# RTxController.net
KiCad netlist of a schematic drawn in EAGLE
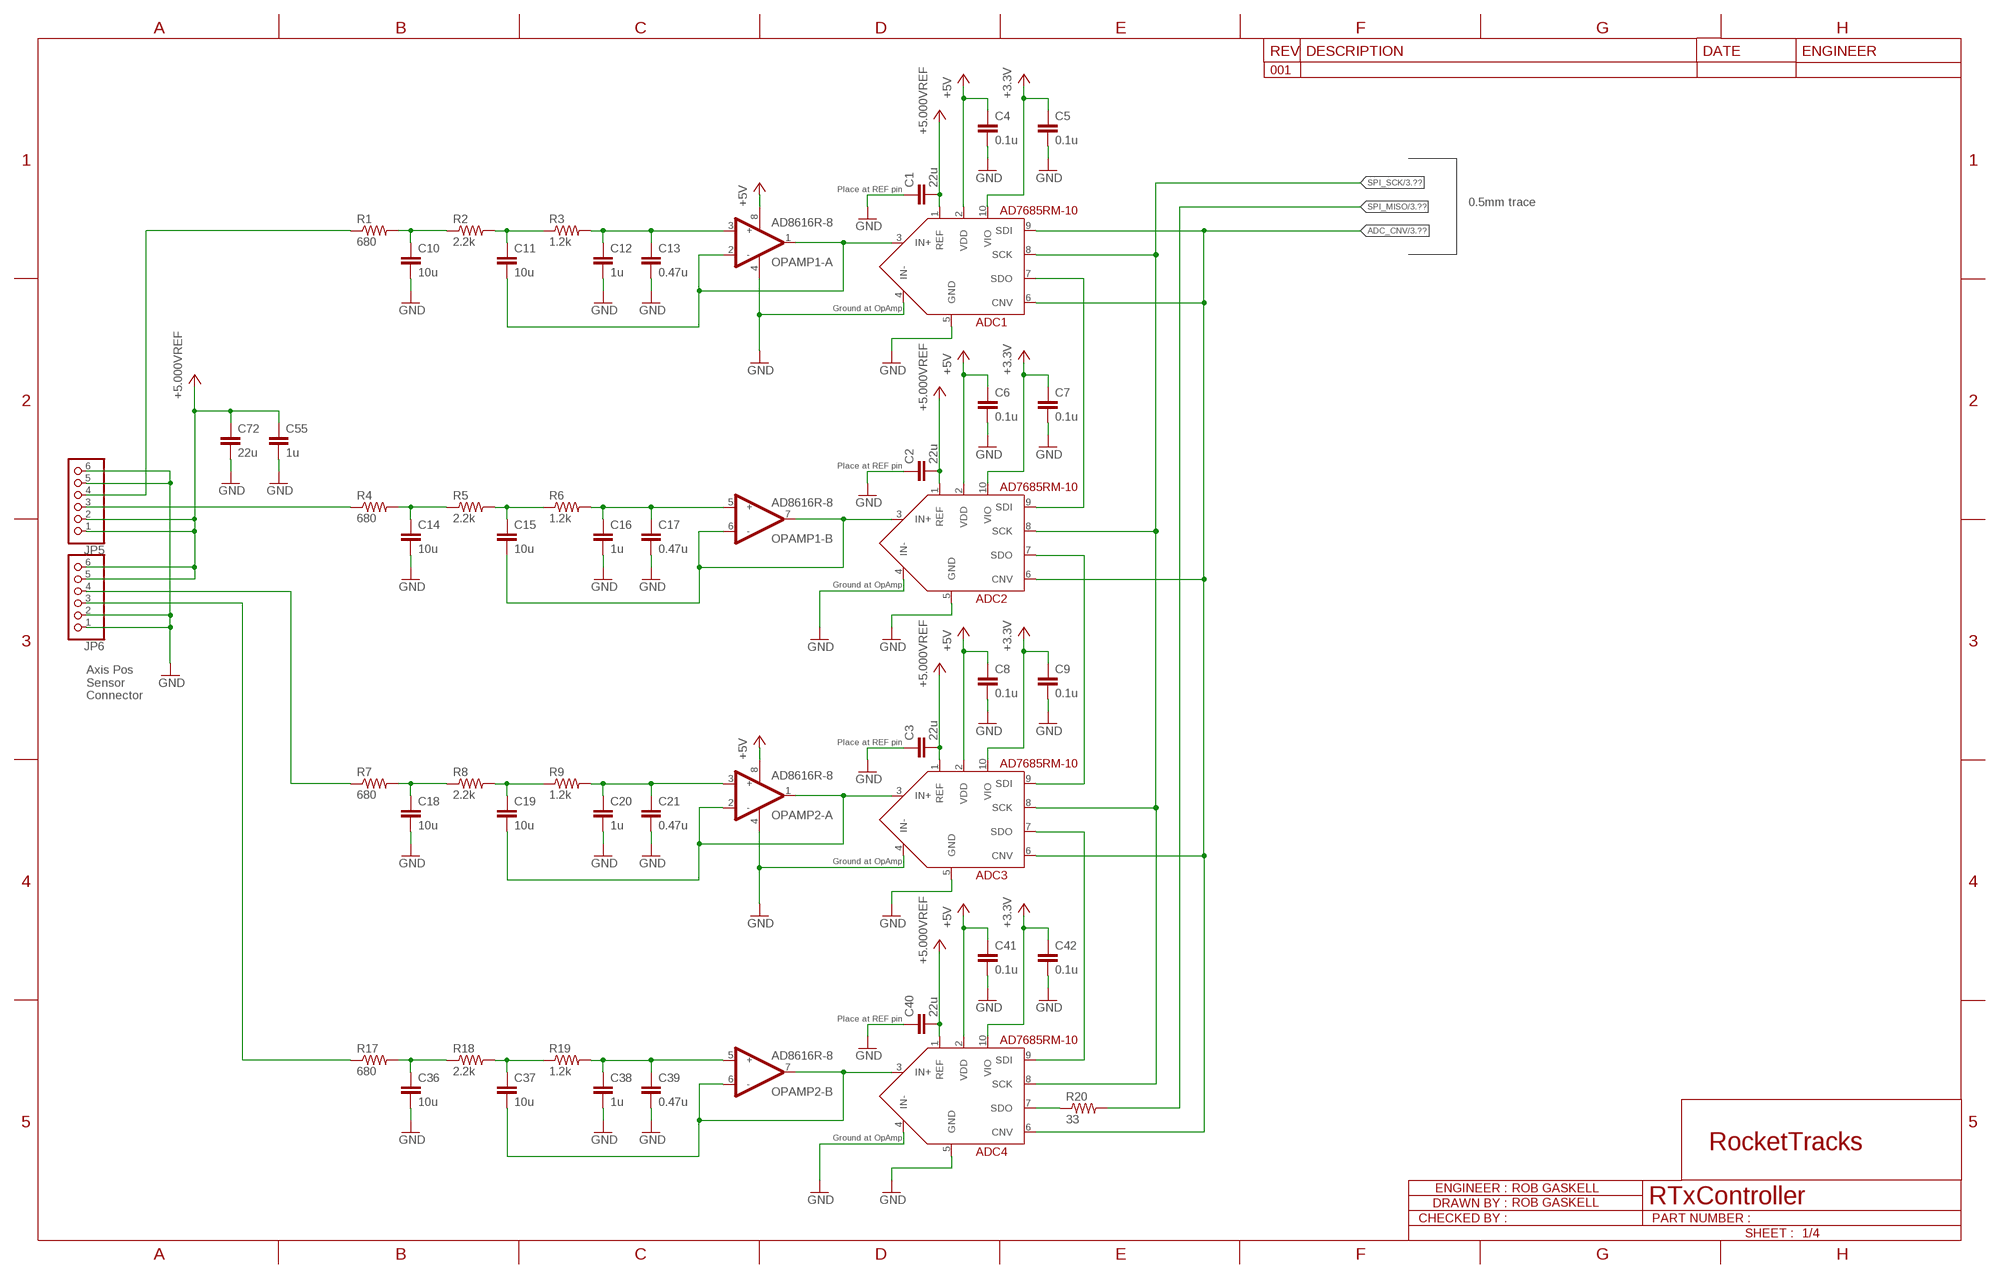
[diagram p0: schematic, sheet 1]
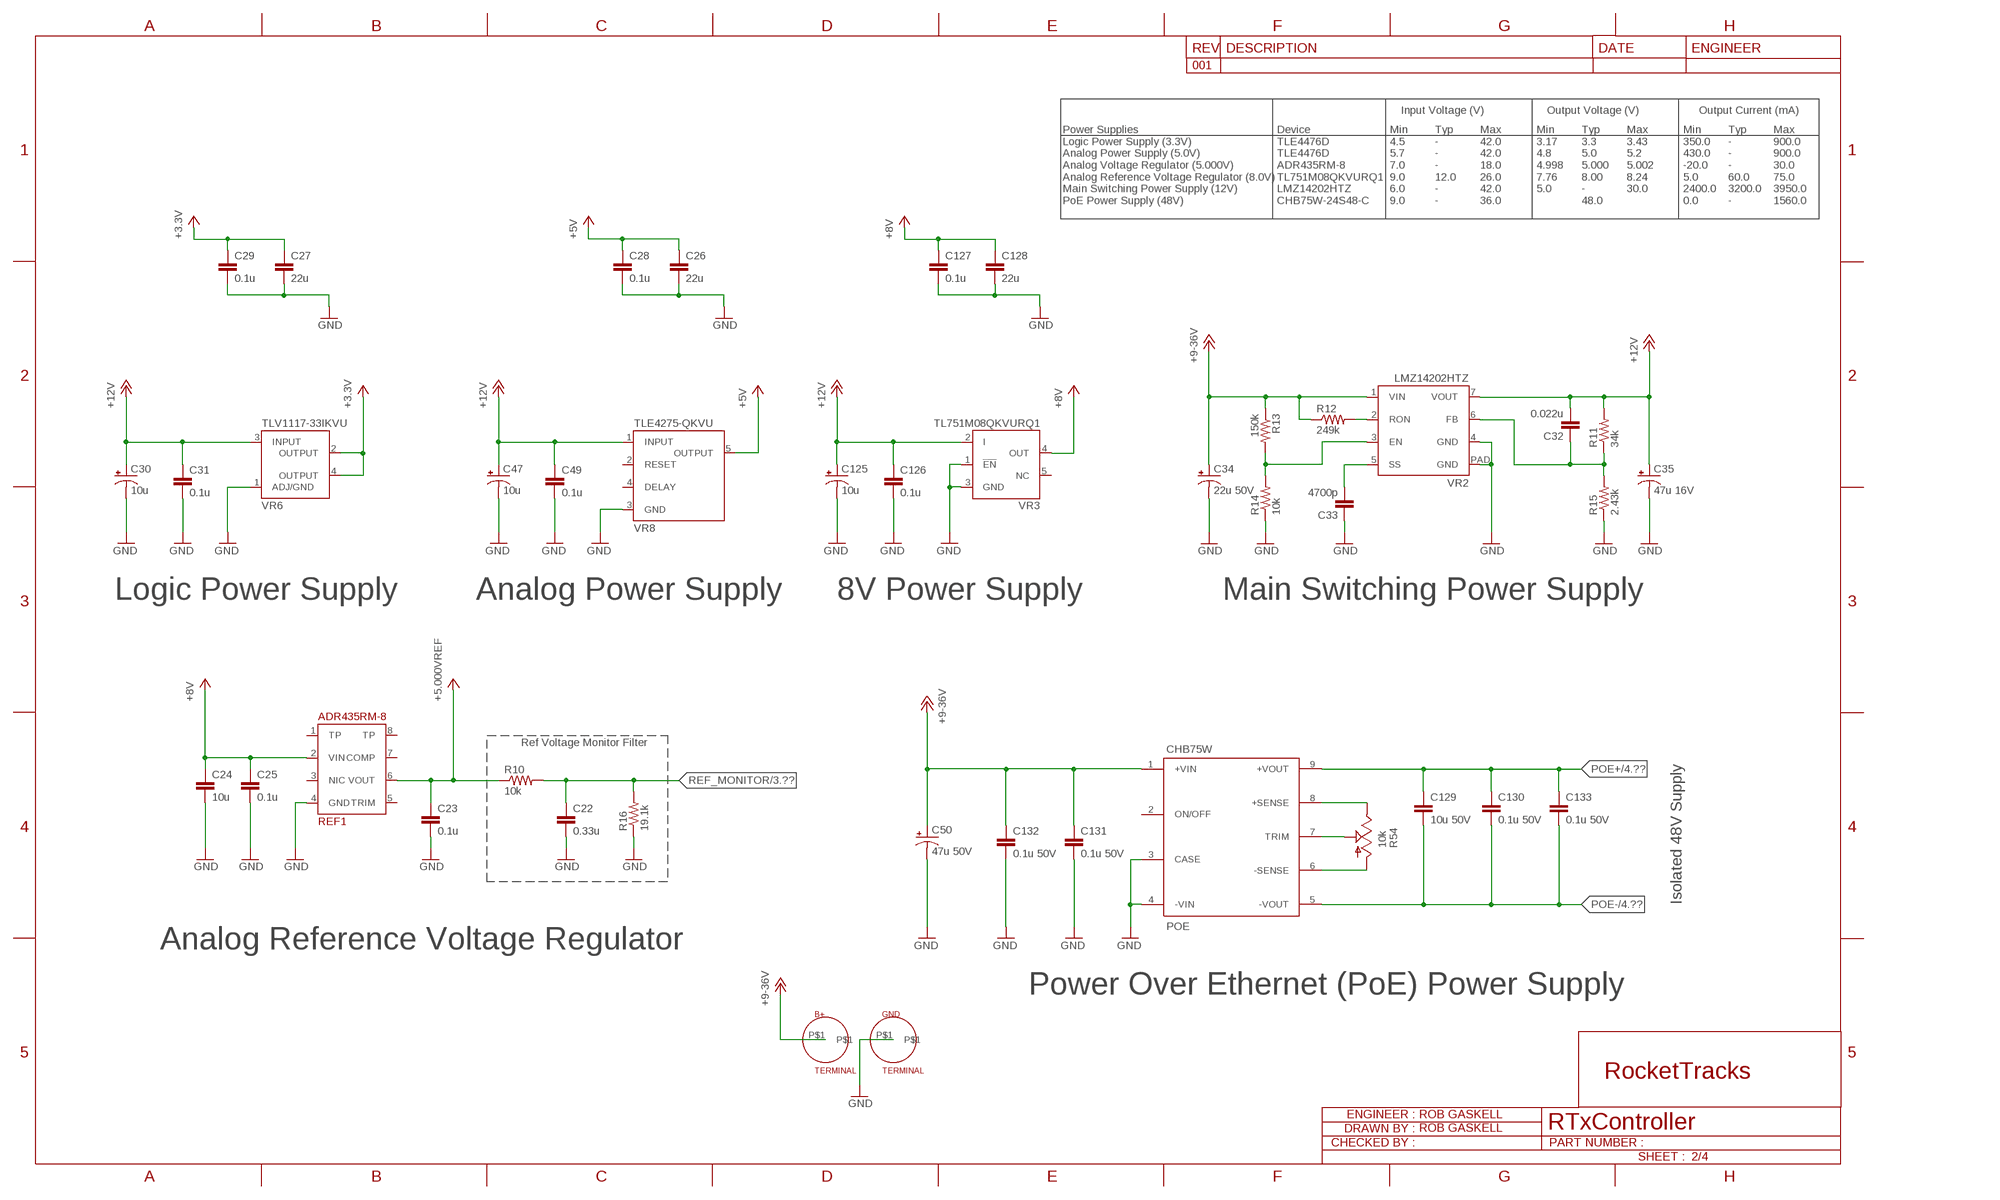
[diagram p1: schematic, sheet 2]
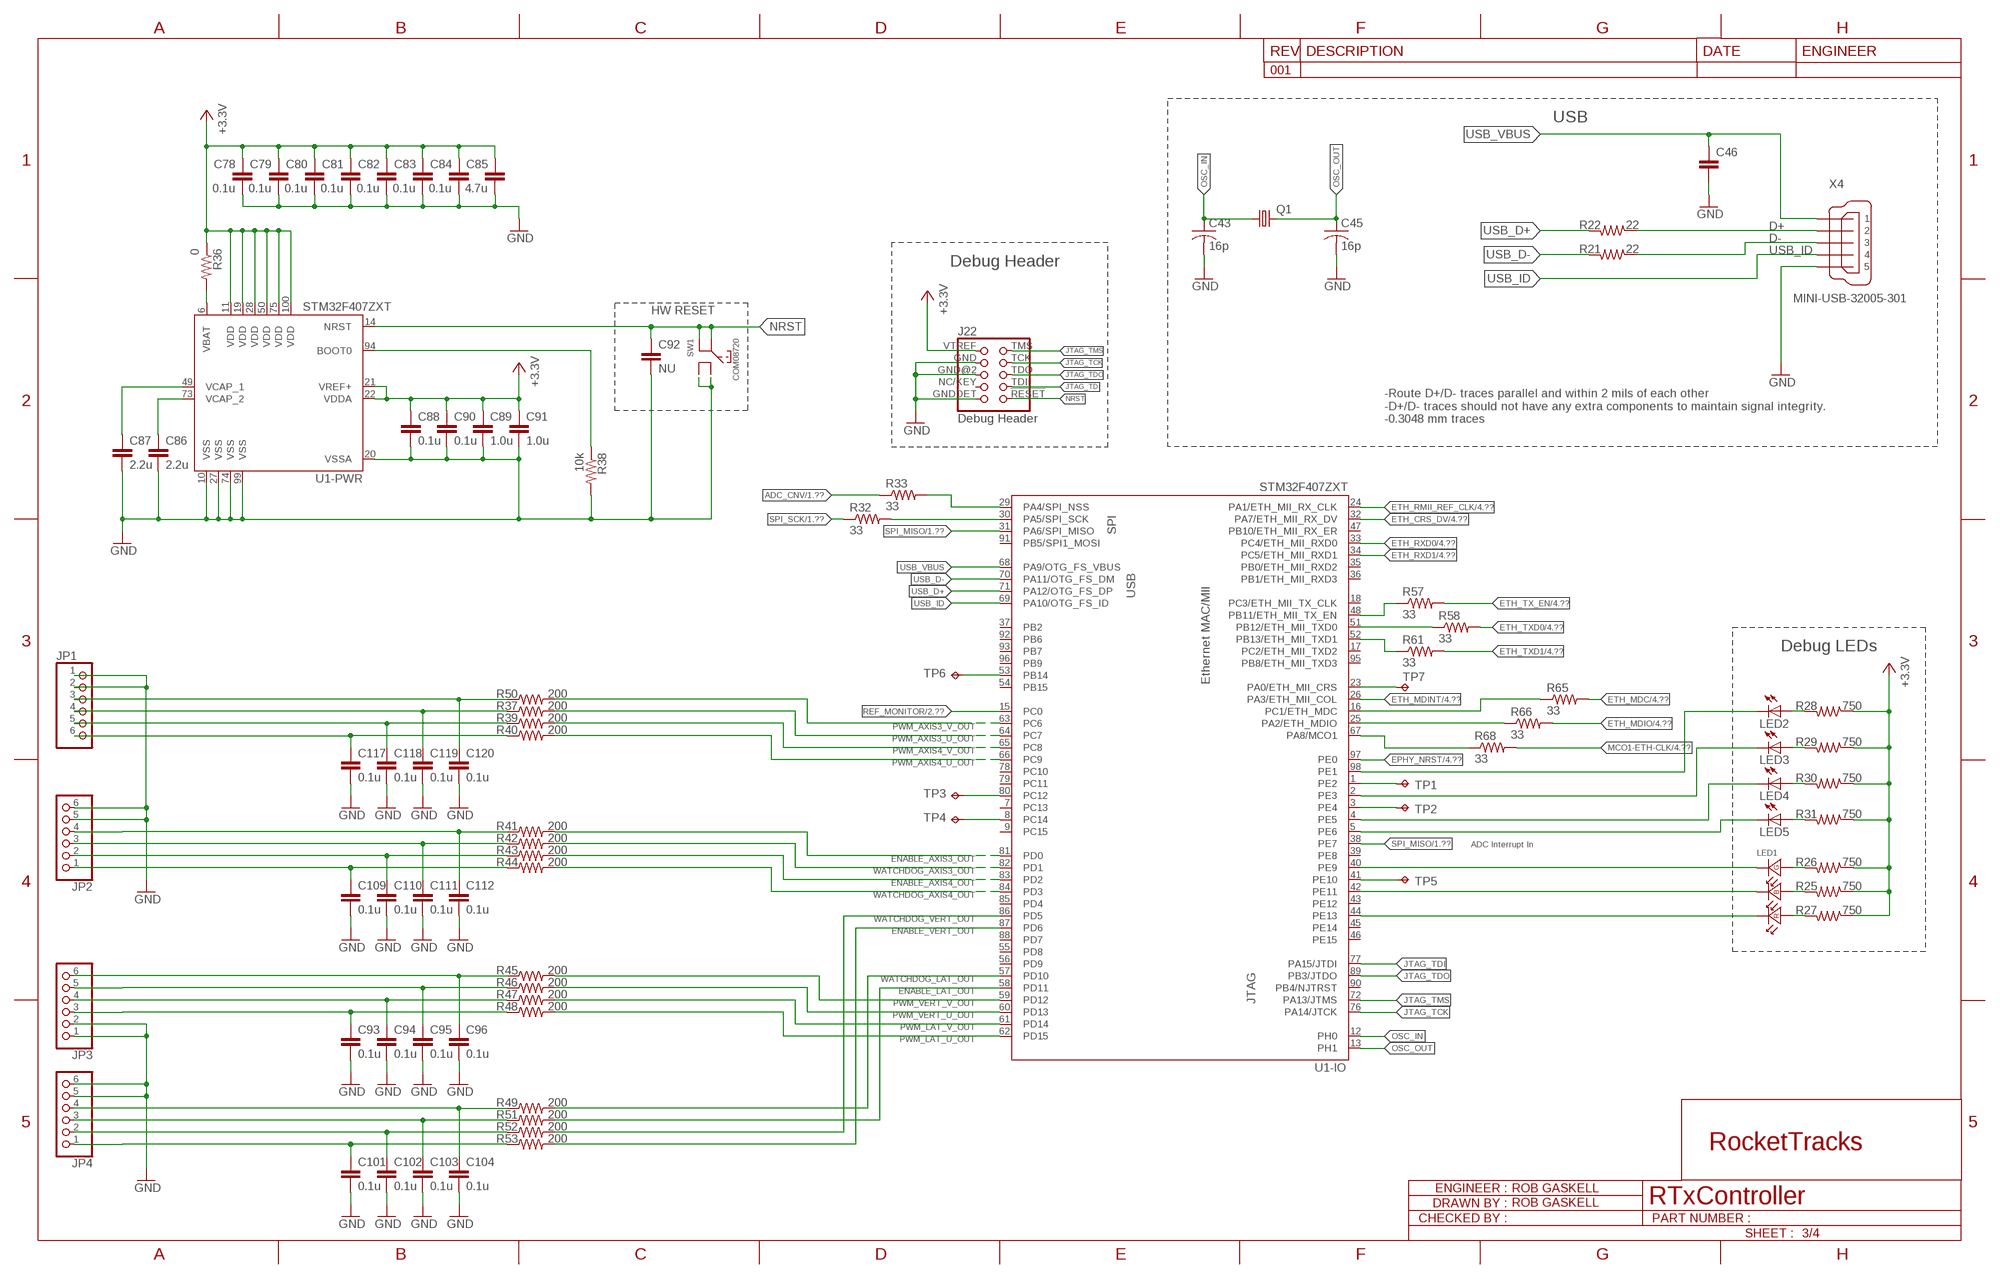
[diagram p2: schematic, sheet 3]
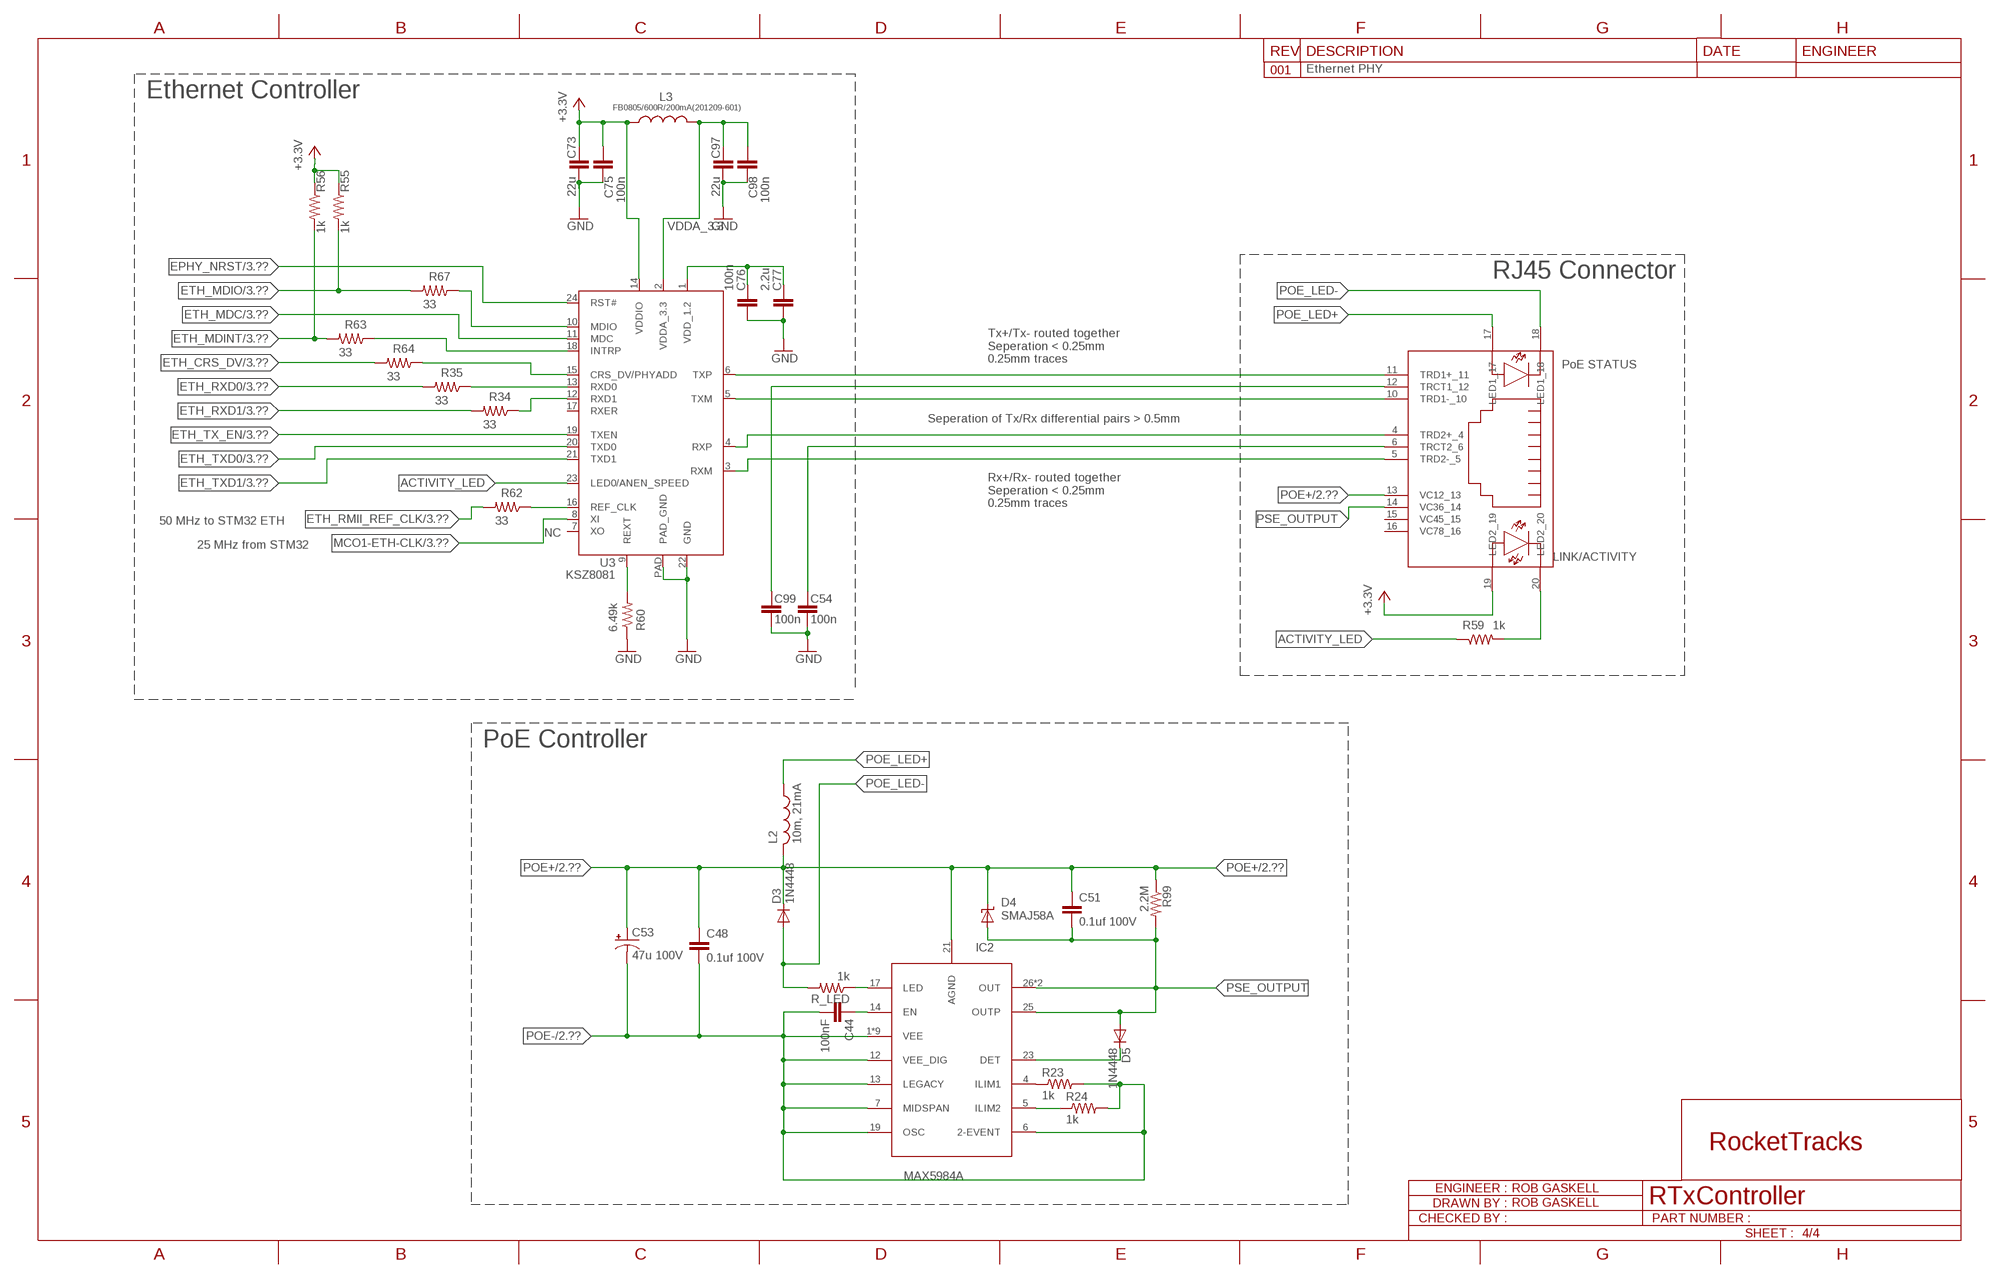
[diagram p3: schematic, sheet 4]

(export (version "E")
  (design (tool "Eeschema 10.0.6"))
  (components
    (comp (ref "C44")
      (value "100nF")
      (footprint "eagle-import:C0805K")
      (libsource (lib "eagle-import") (part "C-EUC0805K"))
    )
    (comp (ref "C48")
      (value "0.1uf 100V")
      (footprint "eagle-import:C0805K")
      (libsource (lib "eagle-import") (part "C-EUC0805K"))
    )
    (comp (ref "C51")
      (value "0.1uf 100V")
      (footprint "eagle-import:C0805K")
      (libsource (lib "eagle-import") (part "C-EUC0805K"))
    )
    (comp (ref "C53")
      (value "47u 100V")
      (footprint "eagle-import:PANASONIC_C")
      (libsource (lib "eagle-import") (part "rcl_CPOL-USC"))
    )
    (comp (ref "C54")
      (value "100n")
      (footprint "eagle-import:0402-C-NOSILK")
      (libsource (lib "eagle-import") (part "C-EU0402-C-NOSILK"))
    )
    (comp (ref "C73")
      (value "22u")
      (footprint "eagle-import:1206-C")
      (libsource (lib "eagle-import") (part "C-EU1206-C"))
    )
    (comp (ref "C75")
      (value "100n")
      (footprint "eagle-import:0402-C-NOSILK")
      (libsource (lib "eagle-import") (part "C-EU0402-C-NOSILK"))
    )
    (comp (ref "C76")
      (value "100n")
      (footprint "eagle-import:0402-C-NOSILK")
      (libsource (lib "eagle-import") (part "C-EU0402-C-NOSILK"))
    )
    (comp (ref "C77")
      (value "2.2u")
      (footprint "eagle-import:0402-C-NOSILK")
      (libsource (lib "eagle-import") (part "C-EU0402-C-NOSILK"))
    )
    (comp (ref "C97")
      (value "22u")
      (footprint "eagle-import:1206-C")
      (libsource (lib "eagle-import") (part "C-EU1206-C"))
    )
    (comp (ref "C98")
      (value "100n")
      (footprint "eagle-import:0402-C-NOSILK")
      (libsource (lib "eagle-import") (part "C-EU0402-C-NOSILK"))
    )
    (comp (ref "C99")
      (value "100n")
      (footprint "eagle-import:0402-C-NOSILK")
      (libsource (lib "eagle-import") (part "C-EU0402-C-NOSILK"))
    )
    (comp (ref "D3")
      (value "1N4448")
      (footprint "eagle-import:SOD-123")
      (libsource (lib "eagle-import") (part "1N4448"))
    )
    (comp (ref "D4")
      (value "SMAJ58A")
      (footprint "eagle-import:SMBJ")
      (libsource (lib "eagle-import") (part "SUPPRESSOR-SMBJ"))
    )
    (comp (ref "D5")
      (value "1N4448")
      (footprint "eagle-import:SOD-123")
      (libsource (lib "eagle-import") (part "1N4448"))
    )
    (comp (ref "IC2")
      (value "MAX5984A")
      (footprint "eagle-import:TQFN-28")
      (libsource (lib "eagle-import") (part "MAX5984"))
    )
    (comp (ref "L2")
      (value "10m, 21mA")
      (footprint "eagle-import:0204V")
      (libsource (lib "eagle-import") (part "L-US0204V"))
    )
    (comp (ref "L3")
      (value "FB0805/600R/200mA(201209-601)")
      (footprint "eagle-import:0805-C-NOSILK")
      (libsource (lib "eagle-import") (part "L-US0805-C-NOSILK"))
    )
    (comp (ref "R23")
      (value "1k")
      (footprint "eagle-import:R0603")
      (libsource (lib "eagle-import") (part "R-US_R0603"))
    )
    (comp (ref "R24")
      (value "1k")
      (footprint "eagle-import:R0603")
      (libsource (lib "eagle-import") (part "R-US_R0603"))
    )
    (comp (ref "R34")
      (value "33")
      (footprint "eagle-import:0402-C-NOSILK")
      (libsource (lib "eagle-import") (part "R-US_0402-C-NOSILK"))
    )
    (comp (ref "R35")
      (value "33")
      (footprint "eagle-import:0402-C-NOSILK")
      (libsource (lib "eagle-import") (part "R-US_0402-C-NOSILK"))
    )
    (comp (ref "R55")
      (value "1k")
      (footprint "eagle-import:0402-C-NOSILK")
      (libsource (lib "eagle-import") (part "R-US_0402-C-NOSILK"))
    )
    (comp (ref "R56")
      (value "1k")
      (footprint "eagle-import:0402-C-NOSILK")
      (libsource (lib "eagle-import") (part "R-US_0402-C-NOSILK"))
    )
    (comp (ref "R59")
      (value "1k")
      (footprint "eagle-import:0402-C-NOSILK")
      (libsource (lib "eagle-import") (part "R-US_0402-C-NOSILK"))
    )
    (comp (ref "R60")
      (value "6.49k")
      (footprint "eagle-import:0402-C-NOSILK")
      (libsource (lib "eagle-import") (part "R-US_0402-C-NOSILK"))
    )
    (comp (ref "R62")
      (value "33")
      (footprint "eagle-import:0402-C-NOSILK")
      (libsource (lib "eagle-import") (part "R-US_0402-C-NOSILK"))
    )
    (comp (ref "R63")
      (value "33")
      (footprint "eagle-import:0402-C-NOSILK")
      (libsource (lib "eagle-import") (part "R-US_0402-C-NOSILK"))
    )
    (comp (ref "R64")
      (value "33")
      (footprint "eagle-import:0402-C-NOSILK")
      (libsource (lib "eagle-import") (part "R-US_0402-C-NOSILK"))
    )
    (comp (ref "R67")
      (value "33")
      (footprint "eagle-import:0402-C-NOSILK")
      (libsource (lib "eagle-import") (part "R-US_0402-C-NOSILK"))
    )
    (comp (ref "R99")
      (value "2.2M")
      (footprint "eagle-import:R0603")
      (libsource (lib "eagle-import") (part "R-US_R0603"))
    )
    (comp (ref "R_LED")
      (value "1k")
      (footprint "eagle-import:R0603")
      (libsource (lib "eagle-import") (part "R-US_R0603"))
    )
    (comp (ref "U3")
      (value "KSZ8081")
      (footprint "eagle-import:QFN-24")
      (libsource (lib "eagle-import") (part "KSZ8081"))
    )
    (comp (ref "X8")
      (value "0826-1X1T-GJ-F")
      (footprint "eagle-import:MAGJACK-RJ45")
      (libsource (lib "eagle-import") (part "0826-1X1T-GJ-F"))
    )
    (comp (ref "B+")
      (value "TERMINAL")
      (footprint "eagle-import:TERMINAL_RELAY")
      (libsource (lib "eagle-import") (part "TERMINAL"))
    )
    (comp (ref "C22")
      (value "0.33u")
      (footprint "eagle-import:C0603")
      (libsource (lib "eagle-import") (part "C-EUC0603"))
    )
    (comp (ref "C23")
      (value "0.1u")
      (footprint "eagle-import:C0402")
      (libsource (lib "eagle-import") (part "C-EUC0402"))
    )
    (comp (ref "C24")
      (value "10u")
      (footprint "eagle-import:C1206")
      (libsource (lib "eagle-import") (part "C-EUC1206"))
    )
    (comp (ref "C25")
      (value "0.1u")
      (footprint "eagle-import:C0402")
      (libsource (lib "eagle-import") (part "C-EUC0402"))
    )
    (comp (ref "C26")
      (value "22u")
      (footprint "eagle-import:C1206")
      (libsource (lib "eagle-import") (part "C-EUC1206"))
    )
    (comp (ref "C27")
      (value "22u")
      (footprint "eagle-import:C1206")
      (libsource (lib "eagle-import") (part "C-EUC1206"))
    )
    (comp (ref "C28")
      (value "0.1u")
      (footprint "eagle-import:C0402")
      (libsource (lib "eagle-import") (part "C-EUC0402"))
    )
    (comp (ref "C29")
      (value "0.1u")
      (footprint "eagle-import:C0402")
      (libsource (lib "eagle-import") (part "C-EUC0402"))
    )
    (comp (ref "C30")
      (value "10u")
      (footprint "eagle-import:PANASONIC_B")
      (libsource (lib "eagle-import") (part "CPOL-USB"))
    )
    (comp (ref "C31")
      (value "0.1u")
      (footprint "eagle-import:C0402")
      (libsource (lib "eagle-import") (part "C-EUC0402"))
    )
    (comp (ref "C32")
      (value "0.022u")
      (footprint "eagle-import:C0402")
      (libsource (lib "eagle-import") (part "C-EUC0402"))
    )
    (comp (ref "C33")
      (value "4700p")
      (footprint "eagle-import:C0402")
      (libsource (lib "eagle-import") (part "C-EUC0402"))
    )
    (comp (ref "C34")
      (value "22u 50V")
      (footprint "eagle-import:PANASONIC_B")
      (libsource (lib "eagle-import") (part "CPOL-USB"))
    )
    (comp (ref "C35")
      (value "47u 16V")
      (footprint "eagle-import:PANASONIC_B")
      (libsource (lib "eagle-import") (part "CPOL-USB"))
    )
    (comp (ref "C47")
      (value "10u")
      (footprint "eagle-import:PANASONIC_B")
      (libsource (lib "eagle-import") (part "CPOL-USB"))
    )
    (comp (ref "C49")
      (value "0.1u")
      (footprint "eagle-import:C0402")
      (libsource (lib "eagle-import") (part "C-EUC0402"))
    )
    (comp (ref "C50")
      (value "47u 50V")
      (footprint "eagle-import:PANASONIC_C")
      (libsource (lib "eagle-import") (part "rcl_CPOL-USC"))
    )
    (comp (ref "C125")
      (value "10u")
      (footprint "eagle-import:PANASONIC_B")
      (libsource (lib "eagle-import") (part "CPOL-USB"))
    )
    (comp (ref "C126")
      (value "0.1u")
      (footprint "eagle-import:C0402")
      (libsource (lib "eagle-import") (part "C-EUC0402"))
    )
    (comp (ref "C127")
      (value "0.1u")
      (footprint "eagle-import:C0402")
      (libsource (lib "eagle-import") (part "C-EUC0402"))
    )
    (comp (ref "C128")
      (value "22u")
      (footprint "eagle-import:C1206")
      (libsource (lib "eagle-import") (part "C-EUC1206"))
    )
    (comp (ref "C129")
      (value "10u 50V")
      (footprint "eagle-import:C1206")
      (libsource (lib "eagle-import") (part "C-EUC1206"))
    )
    (comp (ref "C130")
      (value "0.1u 50V")
      (footprint "eagle-import:C0402")
      (libsource (lib "eagle-import") (part "C-EUC0402"))
    )
    (comp (ref "C131")
      (value "0.1u 50V")
      (footprint "eagle-import:C0402")
      (libsource (lib "eagle-import") (part "C-EUC0402"))
    )
    (comp (ref "C132")
      (value "0.1u 50V")
      (footprint "eagle-import:C0402")
      (libsource (lib "eagle-import") (part "C-EUC0402"))
    )
    (comp (ref "C133")
      (value "0.1u 50V")
      (footprint "eagle-import:C0402")
      (libsource (lib "eagle-import") (part "C-EUC0402"))
    )
    (comp (ref "GND")
      (value "TERMINAL")
      (footprint "eagle-import:TERMINAL_RELAY")
      (libsource (lib "eagle-import") (part "TERMINAL"))
    )
    (comp (ref "POE")
      (value "CHB75W")
      (footprint "eagle-import:CHB75W")
      (libsource (lib "eagle-import") (part "CHB75W"))
    )
    (comp (ref "R10")
      (value "10k")
      (footprint "eagle-import:R0402")
      (libsource (lib "eagle-import") (part "R-US_R0402"))
    )
    (comp (ref "R11")
      (value "34k")
      (footprint "eagle-import:R0603")
      (libsource (lib "eagle-import") (part "R-US_R0603"))
    )
    (comp (ref "R12")
      (value "249k")
      (footprint "eagle-import:R0603")
      (libsource (lib "eagle-import") (part "R-US_R0603"))
    )
    (comp (ref "R13")
      (value "150k")
      (footprint "eagle-import:R0603")
      (libsource (lib "eagle-import") (part "R-US_R0603"))
    )
    (comp (ref "R14")
      (value "10k")
      (footprint "eagle-import:R0603")
      (libsource (lib "eagle-import") (part "R-US_R0603"))
    )
    (comp (ref "R15")
      (value "2.43k")
      (footprint "eagle-import:R0603")
      (libsource (lib "eagle-import") (part "R-US_R0603"))
    )
    (comp (ref "R16")
      (value "19.1k")
      (footprint "eagle-import:R0402")
      (libsource (lib "eagle-import") (part "R-US_R0402"))
    )
    (comp (ref "R54")
      (value "10k")
      (footprint "eagle-import:3223W")
      (libsource (lib "eagle-import") (part "TRIM_US-3223W"))
    )
    (comp (ref "REF1")
      (value "ADR435RM-8")
      (footprint "eagle-import:SOIC8")
      (libsource (lib "eagle-import") (part "ADR435RM-8"))
    )
    (comp (ref "VR2")
      (value "LMZ14202HTZ")
      (footprint "eagle-import:PFM-7")
      (libsource (lib "eagle-import") (part "LMZ14202HTZ"))
    )
    (comp (ref "VR3")
      (value "TL751M08QKVURQ1")
      (footprint "eagle-import:PG-TO252-5-11")
      (libsource (lib "eagle-import") (part "TL751M08QKVURQ1"))
    )
    (comp (ref "VR6")
      (value "TLV1117-33IKVU")
      (footprint "eagle-import:PG-TO252-3-11")
      (libsource (lib "eagle-import") (part "TLV1117-33IKVU"))
    )
    (comp (ref "VR8")
      (value "TLE4275-QKVU")
      (footprint "eagle-import:PG-TO252-5-11")
      (libsource (lib "eagle-import") (part "TLE4275-QKVU"))
    )
    (comp (ref "ADC1")
      (value "AD7685RM-10")
      (footprint "eagle-import:MSOP-10")
      (libsource (lib "eagle-import") (part "AD7685RM-10"))
    )
    (comp (ref "ADC2")
      (value "AD7685RM-10")
      (footprint "eagle-import:MSOP-10")
      (libsource (lib "eagle-import") (part "AD7685RM-10"))
    )
    (comp (ref "ADC3")
      (value "AD7685RM-10")
      (footprint "eagle-import:MSOP-10")
      (libsource (lib "eagle-import") (part "AD7685RM-10"))
    )
    (comp (ref "ADC4")
      (value "AD7685RM-10")
      (footprint "eagle-import:MSOP-10")
      (libsource (lib "eagle-import") (part "AD7685RM-10"))
    )
    (comp (ref "C1")
      (value "22u")
      (footprint "eagle-import:C1206")
      (libsource (lib "eagle-import") (part "C-EUC1206"))
    )
    (comp (ref "C2")
      (value "22u")
      (footprint "eagle-import:C1206")
      (libsource (lib "eagle-import") (part "C-EUC1206"))
    )
    (comp (ref "C3")
      (value "22u")
      (footprint "eagle-import:C1206")
      (libsource (lib "eagle-import") (part "C-EUC1206"))
    )
    (comp (ref "C4")
      (value "0.1u")
      (footprint "eagle-import:C0402")
      (libsource (lib "eagle-import") (part "C-EUC0402"))
    )
    (comp (ref "C5")
      (value "0.1u")
      (footprint "eagle-import:C0402")
      (libsource (lib "eagle-import") (part "C-EUC0402"))
    )
    (comp (ref "C6")
      (value "0.1u")
      (footprint "eagle-import:C0402")
      (libsource (lib "eagle-import") (part "C-EUC0402"))
    )
    (comp (ref "C7")
      (value "0.1u")
      (footprint "eagle-import:C0402")
      (libsource (lib "eagle-import") (part "C-EUC0402"))
    )
    (comp (ref "C8")
      (value "0.1u")
      (footprint "eagle-import:C0402")
      (libsource (lib "eagle-import") (part "C-EUC0402"))
    )
    (comp (ref "C9")
      (value "0.1u")
      (footprint "eagle-import:C0402")
      (libsource (lib "eagle-import") (part "C-EUC0402"))
    )
    (comp (ref "C10")
      (value "10u")
      (footprint "eagle-import:C1206")
      (libsource (lib "eagle-import") (part "C-EUC1206"))
    )
    (comp (ref "C11")
      (value "10u")
      (footprint "eagle-import:C1206")
      (libsource (lib "eagle-import") (part "C-EUC1206"))
    )
    (comp (ref "C12")
      (value "1u")
      (footprint "eagle-import:C0805")
      (libsource (lib "eagle-import") (part "C-EUC0805"))
    )
    (comp (ref "C13")
      (value "0.47u")
      (footprint "eagle-import:C0805")
      (libsource (lib "eagle-import") (part "C-EUC0805"))
    )
    (comp (ref "C14")
      (value "10u")
      (footprint "eagle-import:C1206")
      (libsource (lib "eagle-import") (part "C-EUC1206"))
    )
    (comp (ref "C15")
      (value "10u")
      (footprint "eagle-import:C1206")
      (libsource (lib "eagle-import") (part "C-EUC1206"))
    )
    (comp (ref "C16")
      (value "1u")
      (footprint "eagle-import:C0805")
      (libsource (lib "eagle-import") (part "C-EUC0805"))
    )
    (comp (ref "C17")
      (value "0.47u")
      (footprint "eagle-import:C0805")
      (libsource (lib "eagle-import") (part "C-EUC0805"))
    )
    (comp (ref "C18")
      (value "10u")
      (footprint "eagle-import:C1206")
      (libsource (lib "eagle-import") (part "C-EUC1206"))
    )
    (comp (ref "C19")
      (value "10u")
      (footprint "eagle-import:C1206")
      (libsource (lib "eagle-import") (part "C-EUC1206"))
    )
    (comp (ref "C20")
      (value "1u")
      (footprint "eagle-import:C0805")
      (libsource (lib "eagle-import") (part "C-EUC0805"))
    )
    (comp (ref "C21")
      (value "0.47u")
      (footprint "eagle-import:C0805")
      (libsource (lib "eagle-import") (part "C-EUC0805"))
    )
    (comp (ref "C36")
      (value "10u")
      (footprint "eagle-import:C1206")
      (libsource (lib "eagle-import") (part "C-EUC1206"))
    )
    (comp (ref "C37")
      (value "10u")
      (footprint "eagle-import:C1206")
      (libsource (lib "eagle-import") (part "C-EUC1206"))
    )
    (comp (ref "C38")
      (value "1u")
      (footprint "eagle-import:C0805")
      (libsource (lib "eagle-import") (part "C-EUC0805"))
    )
    (comp (ref "C39")
      (value "0.47u")
      (footprint "eagle-import:C0805")
      (libsource (lib "eagle-import") (part "C-EUC0805"))
    )
    (comp (ref "C40")
      (value "22u")
      (footprint "eagle-import:C1206")
      (libsource (lib "eagle-import") (part "C-EUC1206"))
    )
    (comp (ref "C41")
      (value "0.1u")
      (footprint "eagle-import:C0402")
      (libsource (lib "eagle-import") (part "C-EUC0402"))
    )
    (comp (ref "C42")
      (value "0.1u")
      (footprint "eagle-import:C0402")
      (libsource (lib "eagle-import") (part "C-EUC0402"))
    )
    (comp (ref "C55")
      (value "1u")
      (footprint "eagle-import:C0805")
      (libsource (lib "eagle-import") (part "C-EUC0805"))
    )
    (comp (ref "C72")
      (value "22u")
      (footprint "eagle-import:C1206")
      (libsource (lib "eagle-import") (part "C-EUC1206"))
    )
    (comp (ref "JP5")
      (value "PINHD-1X6")
      (footprint "eagle-import:1X06")
      (libsource (lib "eagle-import") (part "PINHD-1X6"))
    )
    (comp (ref "JP6")
      (value "PINHD-1X6")
      (footprint "eagle-import:1X06")
      (libsource (lib "eagle-import") (part "PINHD-1X6"))
    )
    (comp (ref "OPAMP1")
      (value "AD8616R-8")
      (footprint "eagle-import:SOIC8")
      (libsource (lib "eagle-import") (part "AD8616R-8"))
    )
    (comp (ref "OPAMP2")
      (value "AD8616R-8")
      (footprint "eagle-import:SOIC8")
      (libsource (lib "eagle-import") (part "AD8616R-8"))
    )
    (comp (ref "R1")
      (value "680")
      (footprint "eagle-import:R0402")
      (libsource (lib "eagle-import") (part "R-US_R0402"))
    )
    (comp (ref "R2")
      (value "2.2k")
      (footprint "eagle-import:R0402")
      (libsource (lib "eagle-import") (part "R-US_R0402"))
    )
    (comp (ref "R3")
      (value "1.2k")
      (footprint "eagle-import:R0402")
      (libsource (lib "eagle-import") (part "R-US_R0402"))
    )
    (comp (ref "R4")
      (value "680")
      (footprint "eagle-import:R0402")
      (libsource (lib "eagle-import") (part "R-US_R0402"))
    )
    (comp (ref "R5")
      (value "2.2k")
      (footprint "eagle-import:R0402")
      (libsource (lib "eagle-import") (part "R-US_R0402"))
    )
    (comp (ref "R6")
      (value "1.2k")
      (footprint "eagle-import:R0402")
      (libsource (lib "eagle-import") (part "R-US_R0402"))
    )
    (comp (ref "R7")
      (value "680")
      (footprint "eagle-import:R0402")
      (libsource (lib "eagle-import") (part "R-US_R0402"))
    )
    (comp (ref "R8")
      (value "2.2k")
      (footprint "eagle-import:R0402")
      (libsource (lib "eagle-import") (part "R-US_R0402"))
    )
    (comp (ref "R9")
      (value "1.2k")
      (footprint "eagle-import:R0402")
      (libsource (lib "eagle-import") (part "R-US_R0402"))
    )
    (comp (ref "R17")
      (value "680")
      (footprint "eagle-import:R0402")
      (libsource (lib "eagle-import") (part "R-US_R0402"))
    )
    (comp (ref "R18")
      (value "2.2k")
      (footprint "eagle-import:R0402")
      (libsource (lib "eagle-import") (part "R-US_R0402"))
    )
    (comp (ref "R19")
      (value "1.2k")
      (footprint "eagle-import:R0402")
      (libsource (lib "eagle-import") (part "R-US_R0402"))
    )
    (comp (ref "R20")
      (value "33")
      (footprint "eagle-import:R0402")
      (libsource (lib "eagle-import") (part "R-US_R0402"))
    )
    (comp (ref "C43")
      (value "16p")
      (footprint "eagle-import:C0402")
      (libsource (lib "eagle-import") (part "C-USC0402"))
    )
    (comp (ref "C45")
      (value "16p")
      (footprint "eagle-import:C0402")
      (libsource (lib "eagle-import") (part "C-USC0402"))
    )
    (comp (ref "C46")
      (value "C-EUC0603")
      (footprint "eagle-import:C0603")
      (libsource (lib "eagle-import") (part "rcl_C-EUC0603"))
    )
    (comp (ref "C78")
      (value "0.1u")
      (footprint "eagle-import:C0402")
      (libsource (lib "eagle-import") (part "C-EUC0402"))
    )
    (comp (ref "C79")
      (value "0.1u")
      (footprint "eagle-import:C0402")
      (libsource (lib "eagle-import") (part "C-EUC0402"))
    )
    (comp (ref "C80")
      (value "0.1u")
      (footprint "eagle-import:C0402")
      (libsource (lib "eagle-import") (part "C-EUC0402"))
    )
    (comp (ref "C81")
      (value "0.1u")
      (footprint "eagle-import:C0402")
      (libsource (lib "eagle-import") (part "C-EUC0402"))
    )
    (comp (ref "C82")
      (value "0.1u")
      (footprint "eagle-import:C0402")
      (libsource (lib "eagle-import") (part "C-EUC0402"))
    )
    (comp (ref "C83")
      (value "0.1u")
      (footprint "eagle-import:C0402")
      (libsource (lib "eagle-import") (part "C-EUC0402"))
    )
    (comp (ref "C84")
      (value "0.1u")
      (footprint "eagle-import:C0402")
      (libsource (lib "eagle-import") (part "C-EUC0402"))
    )
    (comp (ref "C85")
      (value "4.7u")
      (footprint "eagle-import:C0603")
      (libsource (lib "eagle-import") (part "C-EUC0603"))
    )
    (comp (ref "C86")
      (value "2.2u")
      (footprint "eagle-import:C0402")
      (libsource (lib "eagle-import") (part "C-EUC0402"))
    )
    (comp (ref "C87")
      (value "2.2u")
      (footprint "eagle-import:C0402")
      (libsource (lib "eagle-import") (part "C-EUC0402"))
    )
    (comp (ref "C88")
      (value "0.1u")
      (footprint "eagle-import:C0402")
      (libsource (lib "eagle-import") (part "C-EUC0402"))
    )
    (comp (ref "C89")
      (value "1.0u")
      (footprint "eagle-import:C0402")
      (libsource (lib "eagle-import") (part "C-EUC0402"))
    )
    (comp (ref "C90")
      (value "0.1u")
      (footprint "eagle-import:C0402")
      (libsource (lib "eagle-import") (part "C-EUC0402"))
    )
    (comp (ref "C91")
      (value "1.0u")
      (footprint "eagle-import:C0402")
      (libsource (lib "eagle-import") (part "C-EUC0402"))
    )
    (comp (ref "C92")
      (value "NU")
      (footprint "eagle-import:C0402")
      (libsource (lib "eagle-import") (part "C-EUC0402"))
    )
    (comp (ref "C93")
      (value "0.1u")
      (footprint "eagle-import:C0603")
      (libsource (lib "eagle-import") (part "C-EUC0603"))
    )
    (comp (ref "C94")
      (value "0.1u")
      (footprint "eagle-import:C0603")
      (libsource (lib "eagle-import") (part "C-EUC0603"))
    )
    (comp (ref "C95")
      (value "0.1u")
      (footprint "eagle-import:C0603")
      (libsource (lib "eagle-import") (part "C-EUC0603"))
    )
    (comp (ref "C96")
      (value "0.1u")
      (footprint "eagle-import:C0603")
      (libsource (lib "eagle-import") (part "C-EUC0603"))
    )
    (comp (ref "C101")
      (value "0.1u")
      (footprint "eagle-import:C0603")
      (libsource (lib "eagle-import") (part "C-EUC0603"))
    )
    (comp (ref "C102")
      (value "0.1u")
      (footprint "eagle-import:C0603")
      (libsource (lib "eagle-import") (part "C-EUC0603"))
    )
    (comp (ref "C103")
      (value "0.1u")
      (footprint "eagle-import:C0603")
      (libsource (lib "eagle-import") (part "C-EUC0603"))
    )
    (comp (ref "C104")
      (value "0.1u")
      (footprint "eagle-import:C0603")
      (libsource (lib "eagle-import") (part "C-EUC0603"))
    )
    (comp (ref "C109")
      (value "0.1u")
      (footprint "eagle-import:C0603")
      (libsource (lib "eagle-import") (part "C-EUC0603"))
    )
    (comp (ref "C110")
      (value "0.1u")
      (footprint "eagle-import:C0603")
      (libsource (lib "eagle-import") (part "C-EUC0603"))
    )
    (comp (ref "C111")
      (value "0.1u")
      (footprint "eagle-import:C0603")
      (libsource (lib "eagle-import") (part "C-EUC0603"))
    )
    (comp (ref "C112")
      (value "0.1u")
      (footprint "eagle-import:C0603")
      (libsource (lib "eagle-import") (part "C-EUC0603"))
    )
    (comp (ref "C117")
      (value "0.1u")
      (footprint "eagle-import:C0603")
      (libsource (lib "eagle-import") (part "C-EUC0603"))
    )
    (comp (ref "C118")
      (value "0.1u")
      (footprint "eagle-import:C0603")
      (libsource (lib "eagle-import") (part "C-EUC0603"))
    )
    (comp (ref "C119")
      (value "0.1u")
      (footprint "eagle-import:C0603")
      (libsource (lib "eagle-import") (part "C-EUC0603"))
    )
    (comp (ref "C120")
      (value "0.1u")
      (footprint "eagle-import:C0603")
      (libsource (lib "eagle-import") (part "C-EUC0603"))
    )
    (comp (ref "J22")
      (value "Debug Header")
      (footprint "eagle-import:1.27MM_2X5")
      (libsource (lib "eagle-import") (part "1.27MM_HDR_2X5"))
    )
    (comp (ref "JP1")
      (value "PINHD-1X6")
      (footprint "eagle-import:1X06")
      (libsource (lib "eagle-import") (part "PINHD-1X6"))
    )
    (comp (ref "JP2")
      (value "PINHD-1X6")
      (footprint "eagle-import:1X06")
      (libsource (lib "eagle-import") (part "PINHD-1X6"))
    )
    (comp (ref "JP3")
      (value "PINHD-1X6")
      (footprint "eagle-import:1X06")
      (libsource (lib "eagle-import") (part "PINHD-1X6"))
    )
    (comp (ref "JP4")
      (value "PINHD-1X6")
      (footprint "eagle-import:1X06")
      (libsource (lib "eagle-import") (part "PINHD-1X6"))
    )
    (comp (ref "LED1")
      (value "LED_RGB_PLCC-6")
      (footprint "eagle-import:PLCC-6")
      (libsource (lib "eagle-import") (part "LED_RGB_PLCC-6"))
    )
    (comp (ref "LED2")
      (value "LEDCHIP-LED0603")
      (footprint "eagle-import:CHIP-LED0603")
      (libsource (lib "eagle-import") (part "LEDCHIP-LED0603"))
    )
    (comp (ref "LED3")
      (value "LEDCHIP-LED0603")
      (footprint "eagle-import:CHIP-LED0603")
      (libsource (lib "eagle-import") (part "LEDCHIP-LED0603"))
    )
    (comp (ref "LED4")
      (value "LEDCHIP-LED0603")
      (footprint "eagle-import:CHIP-LED0603")
      (libsource (lib "eagle-import") (part "LEDCHIP-LED0603"))
    )
    (comp (ref "LED5")
      (value "LEDCHIP-LED0603")
      (footprint "eagle-import:CHIP-LED0603")
      (libsource (lib "eagle-import") (part "LEDCHIP-LED0603"))
    )
    (comp (ref "Q1")
      (value "CRYSTALCTS406")
      (footprint "eagle-import:CTS406")
      (libsource (lib "eagle-import") (part "CRYSTALCTS406"))
    )
    (comp (ref "R21")
      (value "22")
      (footprint "eagle-import:R0402")
      (libsource (lib "eagle-import") (part "rcl_R-US_R0402"))
    )
    (comp (ref "R22")
      (value "22")
      (footprint "eagle-import:R0402")
      (libsource (lib "eagle-import") (part "rcl_R-US_R0402"))
    )
    (comp (ref "R25")
      (value "750")
      (footprint "eagle-import:R0402")
      (libsource (lib "eagle-import") (part "rcl_R-US_R0402"))
    )
    (comp (ref "R26")
      (value "750")
      (footprint "eagle-import:R0402")
      (libsource (lib "eagle-import") (part "rcl_R-US_R0402"))
    )
    (comp (ref "R27")
      (value "750")
      (footprint "eagle-import:R0402")
      (libsource (lib "eagle-import") (part "rcl_R-US_R0402"))
    )
    (comp (ref "R28")
      (value "750")
      (footprint "eagle-import:R0402")
      (libsource (lib "eagle-import") (part "rcl_R-US_R0402"))
    )
    (comp (ref "R29")
      (value "750")
      (footprint "eagle-import:R0402")
      (libsource (lib "eagle-import") (part "rcl_R-US_R0402"))
    )
    (comp (ref "R30")
      (value "750")
      (footprint "eagle-import:R0402")
      (libsource (lib "eagle-import") (part "rcl_R-US_R0402"))
    )
    (comp (ref "R31")
      (value "750")
      (footprint "eagle-import:R0402")
      (libsource (lib "eagle-import") (part "rcl_R-US_R0402"))
    )
    (comp (ref "R32")
      (value "33")
      (footprint "eagle-import:R0402")
      (libsource (lib "eagle-import") (part "R-US_R0402"))
    )
    (comp (ref "R33")
      (value "33")
      (footprint "eagle-import:R0402")
      (libsource (lib "eagle-import") (part "R-US_R0402"))
    )
    (comp (ref "R36")
      (value "0")
      (footprint "eagle-import:R0603")
      (libsource (lib "eagle-import") (part "R-US_R0603"))
    )
    (comp (ref "R37")
      (value "200")
      (footprint "eagle-import:R0603")
      (libsource (lib "eagle-import") (part "R-US_R0603"))
    )
    (comp (ref "R38")
      (value "10k")
      (footprint "eagle-import:R0603")
      (libsource (lib "eagle-import") (part "R-US_R0603"))
    )
    (comp (ref "R39")
      (value "200")
      (footprint "eagle-import:R0603")
      (libsource (lib "eagle-import") (part "R-US_R0603"))
    )
    (comp (ref "R40")
      (value "200")
      (footprint "eagle-import:R0603")
      (libsource (lib "eagle-import") (part "R-US_R0603"))
    )
    (comp (ref "R41")
      (value "200")
      (footprint "eagle-import:R0603")
      (libsource (lib "eagle-import") (part "R-US_R0603"))
    )
    (comp (ref "R42")
      (value "200")
      (footprint "eagle-import:R0603")
      (libsource (lib "eagle-import") (part "R-US_R0603"))
    )
    (comp (ref "R43")
      (value "200")
      (footprint "eagle-import:R0603")
      (libsource (lib "eagle-import") (part "R-US_R0603"))
    )
    (comp (ref "R44")
      (value "200")
      (footprint "eagle-import:R0603")
      (libsource (lib "eagle-import") (part "R-US_R0603"))
    )
    (comp (ref "R45")
      (value "200")
      (footprint "eagle-import:R0603")
      (libsource (lib "eagle-import") (part "R-US_R0603"))
    )
    (comp (ref "R46")
      (value "200")
      (footprint "eagle-import:R0603")
      (libsource (lib "eagle-import") (part "R-US_R0603"))
    )
    (comp (ref "R47")
      (value "200")
      (footprint "eagle-import:R0603")
      (libsource (lib "eagle-import") (part "R-US_R0603"))
    )
    (comp (ref "R48")
      (value "200")
      (footprint "eagle-import:R0603")
      (libsource (lib "eagle-import") (part "R-US_R0603"))
    )
    (comp (ref "R49")
      (value "200")
      (footprint "eagle-import:R0603")
      (libsource (lib "eagle-import") (part "R-US_R0603"))
    )
    (comp (ref "R50")
      (value "200")
      (footprint "eagle-import:R0603")
      (libsource (lib "eagle-import") (part "R-US_R0603"))
    )
    (comp (ref "R51")
      (value "200")
      (footprint "eagle-import:R0603")
      (libsource (lib "eagle-import") (part "R-US_R0603"))
    )
    (comp (ref "R52")
      (value "200")
      (footprint "eagle-import:R0603")
      (libsource (lib "eagle-import") (part "R-US_R0603"))
    )
    (comp (ref "R53")
      (value "200")
      (footprint "eagle-import:R0603")
      (libsource (lib "eagle-import") (part "R-US_R0603"))
    )
    (comp (ref "R57")
      (value "33")
      (footprint "eagle-import:R0402")
      (libsource (lib "eagle-import") (part "R-US_R0402"))
    )
    (comp (ref "R58")
      (value "33")
      (footprint "eagle-import:R0402")
      (libsource (lib "eagle-import") (part "R-US_R0402"))
    )
    (comp (ref "R61")
      (value "33")
      (footprint "eagle-import:R0402")
      (libsource (lib "eagle-import") (part "R-US_R0402"))
    )
    (comp (ref "R65")
      (value "33")
      (footprint "eagle-import:R0402")
      (libsource (lib "eagle-import") (part "R-US_R0402"))
    )
    (comp (ref "R66")
      (value "33")
      (footprint "eagle-import:R0402")
      (libsource (lib "eagle-import") (part "R-US_R0402"))
    )
    (comp (ref "R68")
      (value "33")
      (footprint "eagle-import:R0402")
      (libsource (lib "eagle-import") (part "R-US_R0402"))
    )
    (comp (ref "SW1")
      (value "COM08720")
      (footprint "eagle-import:COM08720")
      (libsource (lib "eagle-import") (part "COM08720"))
    )
    (comp (ref "TP1")
      (value "TPTP06R")
      (footprint "eagle-import:TP06R")
      (libsource (lib "eagle-import") (part "TPTP06R"))
    )
    (comp (ref "TP2")
      (value "TPTP06R")
      (footprint "eagle-import:TP06R")
      (libsource (lib "eagle-import") (part "TPTP06R"))
    )
    (comp (ref "TP3")
      (value "TPTP06R")
      (footprint "eagle-import:TP06R")
      (libsource (lib "eagle-import") (part "TPTP06R"))
    )
    (comp (ref "TP4")
      (value "TPTP06R")
      (footprint "eagle-import:TP06R")
      (libsource (lib "eagle-import") (part "TPTP06R"))
    )
    (comp (ref "TP5")
      (value "TPTP06R")
      (footprint "eagle-import:TP06R")
      (libsource (lib "eagle-import") (part "TPTP06R"))
    )
    (comp (ref "TP6")
      (value "TPTP06R")
      (footprint "eagle-import:TP06R")
      (libsource (lib "eagle-import") (part "TPTP06R"))
    )
    (comp (ref "TP7")
      (value "TPTP06R")
      (footprint "eagle-import:TP06R")
      (libsource (lib "eagle-import") (part "TPTP06R"))
    )
    (comp (ref "U1")
      (value "STM32F407ZXT")
      (footprint "eagle-import:LQFP-100")
      (libsource (lib "eagle-import") (part "STM32F407ZXT"))
    )
    (comp (ref "X4")
      (value "MINI-USB-32005-301")
      (footprint "eagle-import:32005-301")
      (libsource (lib "eagle-import") (part "MINI-USB-32005-301"))
    )
  )
  (nets
    (net (code "1") (name "+3.3V") (class "Default")
      (node (ref "ADC1") (pin "10") (pinfunction "VIO_10") (pintype "power_in"))
      (node (ref "ADC2") (pin "10") (pinfunction "VIO_10") (pintype "power_in"))
      (node (ref "ADC3") (pin "10") (pinfunction "VIO_10") (pintype "power_in"))
      (node (ref "ADC4") (pin "10") (pinfunction "VIO_10") (pintype "power_in"))
      (node (ref "C27") (pin "1") (pinfunction "1_1") (pintype "passive"))
      (node (ref "C29") (pin "1") (pinfunction "1_1") (pintype "passive"))
      (node (ref "C42") (pin "1") (pinfunction "1_1") (pintype "passive"))
      (node (ref "C5") (pin "1") (pinfunction "1_1") (pintype "passive"))
      (node (ref "C7") (pin "1") (pinfunction "1_1") (pintype "passive"))
      (node (ref "C73") (pin "2") (pinfunction "2_2") (pintype "passive"))
      (node (ref "C75") (pin "2") (pinfunction "2_2") (pintype "passive"))
      (node (ref "C78") (pin "1") (pinfunction "1_1") (pintype "passive"))
      (node (ref "C79") (pin "1") (pinfunction "1_1") (pintype "passive"))
      (node (ref "C80") (pin "1") (pinfunction "1_1") (pintype "passive"))
      (node (ref "C81") (pin "1") (pinfunction "1_1") (pintype "passive"))
      (node (ref "C82") (pin "1") (pinfunction "1_1") (pintype "passive"))
      (node (ref "C83") (pin "1") (pinfunction "1_1") (pintype "passive"))
      (node (ref "C84") (pin "1") (pinfunction "1_1") (pintype "passive"))
      (node (ref "C85") (pin "1") (pinfunction "1_1") (pintype "passive"))
      (node (ref "C88") (pin "1") (pinfunction "1_1") (pintype "passive"))
      (node (ref "C89") (pin "1") (pinfunction "1_1") (pintype "passive"))
      (node (ref "C9") (pin "1") (pinfunction "1_1") (pintype "passive"))
      (node (ref "C90") (pin "1") (pinfunction "1_1") (pintype "passive"))
      (node (ref "C91") (pin "1") (pinfunction "1_1") (pintype "passive"))
      (node (ref "J22") (pin "VTREF") (pinfunction "VTREF_VTREF") (pintype "passive"))
      (node (ref "L3") (pin "2") (pinfunction "2_2") (pintype "passive"))
      (node (ref "R25") (pin "1") (pinfunction "1_1") (pintype "passive"))
      (node (ref "R26") (pin "1") (pinfunction "1_1") (pintype "passive"))
      (node (ref "R27") (pin "1") (pinfunction "1_1") (pintype "passive"))
      (node (ref "R28") (pin "1") (pinfunction "1_1") (pintype "passive"))
      (node (ref "R29") (pin "1") (pinfunction "1_1") (pintype "passive"))
      (node (ref "R30") (pin "1") (pinfunction "1_1") (pintype "passive"))
      (node (ref "R31") (pin "1") (pinfunction "1_1") (pintype "passive"))
      (node (ref "R36") (pin "1") (pinfunction "1_1") (pintype "passive"))
      (node (ref "R55") (pin "1") (pinfunction "1_1") (pintype "passive"))
      (node (ref "R56") (pin "1") (pinfunction "1_1") (pintype "passive"))
      (node (ref "U1") (pin "100") (pinfunction "VDD_100") (pintype "power_in"))
      (node (ref "U1") (pin "11") (pinfunction "VDD_11") (pintype "power_in"))
      (node (ref "U1") (pin "19") (pinfunction "VDD_19") (pintype "power_in"))
      (node (ref "U1") (pin "21") (pinfunction "VREF+_21") (pintype "power_in"))
      (node (ref "U1") (pin "22") (pinfunction "VDDA_22") (pintype "power_in"))
      (node (ref "U1") (pin "28") (pinfunction "VDD_28") (pintype "power_in"))
      (node (ref "U1") (pin "50") (pinfunction "VDD_50") (pintype "power_in"))
      (node (ref "U1") (pin "75") (pinfunction "VDD_75") (pintype "power_in"))
      (node (ref "U3") (pin "14") (pinfunction "VDDIO_14") (pintype "power_in"))
      (node (ref "VR6") (pin "2") (pinfunction "OUTPUT_2") (pintype "power_in"))
      (node (ref "VR6") (pin "4") (pinfunction "OUTPUT_4") (pintype "power_in"))
      (node (ref "X8") (pin "19") (pinfunction "LED2_19_19") (pintype "input"))
    )
    (net (code "2") (name "+5.000VREF") (class "Default")
      (node (ref "ADC1") (pin "1") (pinfunction "REF_1") (pintype "power_in"))
      (node (ref "ADC2") (pin "1") (pinfunction "REF_1") (pintype "power_in"))
      (node (ref "ADC3") (pin "1") (pinfunction "REF_1") (pintype "power_in"))
      (node (ref "ADC4") (pin "1") (pinfunction "REF_1") (pintype "power_in"))
      (node (ref "C1") (pin "2") (pinfunction "2_2") (pintype "passive"))
      (node (ref "C2") (pin "2") (pinfunction "2_2") (pintype "passive"))
      (node (ref "C23") (pin "1") (pinfunction "1_1") (pintype "passive"))
      (node (ref "C3") (pin "2") (pinfunction "2_2") (pintype "passive"))
      (node (ref "C40") (pin "2") (pinfunction "2_2") (pintype "passive"))
      (node (ref "C55") (pin "1") (pinfunction "1_1") (pintype "passive"))
      (node (ref "C72") (pin "1") (pinfunction "1_1") (pintype "passive"))
      (node (ref "JP5") (pin "1") (pinfunction "1_1") (pintype "passive"))
      (node (ref "JP5") (pin "2") (pinfunction "2_2") (pintype "passive"))
      (node (ref "JP6") (pin "5") (pinfunction "5_5") (pintype "passive"))
      (node (ref "JP6") (pin "6") (pinfunction "6_6") (pintype "passive"))
      (node (ref "R10") (pin "1") (pinfunction "1_1") (pintype "passive"))
      (node (ref "REF1") (pin "6") (pinfunction "VOUT_6") (pintype "bidirectional"))
    )
    (net (code "3") (name "+5V") (class "Default")
      (node (ref "ADC1") (pin "2") (pinfunction "VDD_2") (pintype "power_in"))
      (node (ref "ADC2") (pin "2") (pinfunction "VDD_2") (pintype "power_in"))
      (node (ref "ADC3") (pin "2") (pinfunction "VDD_2") (pintype "power_in"))
      (node (ref "ADC4") (pin "2") (pinfunction "VDD_2") (pintype "power_in"))
      (node (ref "C26") (pin "1") (pinfunction "1_1") (pintype "passive"))
      (node (ref "C28") (pin "1") (pinfunction "1_1") (pintype "passive"))
      (node (ref "C4") (pin "1") (pinfunction "1_1") (pintype "passive"))
      (node (ref "C41") (pin "1") (pinfunction "1_1") (pintype "passive"))
      (node (ref "C6") (pin "1") (pinfunction "1_1") (pintype "passive"))
      (node (ref "C8") (pin "1") (pinfunction "1_1") (pintype "passive"))
      (node (ref "OPAMP1") (pin "8") (pinfunction "V+_8") (pintype "power_in"))
      (node (ref "OPAMP2") (pin "8") (pinfunction "V+_8") (pintype "power_in"))
      (node (ref "VR8") (pin "5") (pinfunction "OUTPUT_5") (pintype "power_in"))
    )
    (net (code "4") (name "+8V") (class "Default")
      (node (ref "C127") (pin "1") (pinfunction "1_1") (pintype "passive"))
      (node (ref "C128") (pin "1") (pinfunction "1_1") (pintype "passive"))
      (node (ref "C24") (pin "1") (pinfunction "1_1") (pintype "passive"))
      (node (ref "C25") (pin "1") (pinfunction "1_1") (pintype "passive"))
      (node (ref "REF1") (pin "2") (pinfunction "VIN_2") (pintype "bidirectional"))
      (node (ref "VR3") (pin "4") (pinfunction "OUT_4") (pintype "bidirectional"))
    )
    (net (code "5") (name "+9-36V") (class "Default")
      (node (ref "B+") (pin "P$1") (pinfunction "P$1_P$1") (pintype "bidirectional"))
      (node (ref "C131") (pin "1") (pinfunction "1_1") (pintype "passive"))
      (node (ref "C132") (pin "1") (pinfunction "1_1") (pintype "passive"))
      (node (ref "C34") (pin "+") (pinfunction "+_+") (pintype "passive"))
      (node (ref "C50") (pin "+") (pinfunction "+_+") (pintype "passive"))
      (node (ref "POE") (pin "1") (pinfunction "+VIN_1") (pintype "power_in"))
      (node (ref "R12") (pin "1") (pinfunction "1_1") (pintype "passive"))
      (node (ref "R13") (pin "1") (pinfunction "1_1") (pintype "passive"))
      (node (ref "VR2") (pin "1") (pinfunction "VIN_1") (pintype "bidirectional"))
    )
    (net (code "6") (name "+12V") (class "Default")
      (node (ref "C125") (pin "+") (pinfunction "+_+") (pintype "passive"))
      (node (ref "C126") (pin "1") (pinfunction "1_1") (pintype "passive"))
      (node (ref "C30") (pin "+") (pinfunction "+_+") (pintype "passive"))
      (node (ref "C31") (pin "1") (pinfunction "1_1") (pintype "passive"))
      (node (ref "C32") (pin "2") (pinfunction "2_2") (pintype "passive"))
      (node (ref "C35") (pin "+") (pinfunction "+_+") (pintype "passive"))
      (node (ref "C47") (pin "+") (pinfunction "+_+") (pintype "passive"))
      (node (ref "C49") (pin "1") (pinfunction "1_1") (pintype "passive"))
      (node (ref "R11") (pin "2") (pinfunction "2_2") (pintype "passive"))
      (node (ref "VR2") (pin "7") (pinfunction "VOUT_7") (pintype "bidirectional"))
      (node (ref "VR3") (pin "2") (pinfunction "I_2") (pintype "bidirectional"))
      (node (ref "VR6") (pin "3") (pinfunction "INPUT_3") (pintype "power_in"))
      (node (ref "VR8") (pin "1") (pinfunction "INPUT_1") (pintype "power_in"))
    )
    (net (code "7") (name "ACTIVITY_LED") (class "Default")
      (node (ref "R59") (pin "1") (pinfunction "1_1") (pintype "passive"))
      (node (ref "U3") (pin "23") (pinfunction "LED0/ANEN_SPEED_23") (pintype "bidirectional"))
    )
    (net (code "8") (name "ADC_CNV") (class "Default")
      (node (ref "ADC1") (pin "6") (pinfunction "CNV_6") (pintype "input"))
      (node (ref "ADC1") (pin "9") (pinfunction "SDI_9") (pintype "input"))
      (node (ref "ADC2") (pin "6") (pinfunction "CNV_6") (pintype "input"))
      (node (ref "ADC3") (pin "6") (pinfunction "CNV_6") (pintype "input"))
      (node (ref "ADC4") (pin "6") (pinfunction "CNV_6") (pintype "input"))
      (node (ref "R33") (pin "1") (pinfunction "1_1") (pintype "passive"))
    )
    (net (code "9") (name "D+") (class "Default")
      (node (ref "R22") (pin "1") (pinfunction "1_1") (pintype "passive"))
      (node (ref "X4") (pin "2") (pinfunction "2_2") (pintype "passive"))
    )
    (net (code "10") (name "D-") (class "Default")
      (node (ref "R21") (pin "1") (pinfunction "1_1") (pintype "passive"))
      (node (ref "X4") (pin "3") (pinfunction "3_3") (pintype "passive"))
    )
    (net (code "11") (name "ENABLE_AXIS3_OUT") (class "Default")
      (node (ref "R41") (pin "2") (pinfunction "2_2") (pintype "passive"))
      (node (ref "U1") (pin "81") (pinfunction "PD0_81") (pintype "bidirectional"))
    )
    (net (code "12") (name "ENABLE_AXIS4_OUT") (class "Default")
      (node (ref "R43") (pin "2") (pinfunction "2_2") (pintype "passive"))
      (node (ref "U1") (pin "83") (pinfunction "PD2_83") (pintype "bidirectional"))
    )
    (net (code "13") (name "ENABLE_LAT_OUT") (class "Default")
      (node (ref "R51") (pin "2") (pinfunction "2_2") (pintype "passive"))
      (node (ref "U1") (pin "58") (pinfunction "PD11_58") (pintype "bidirectional"))
    )
    (net (code "14") (name "ENABLE_VERT_OUT") (class "Default")
      (node (ref "R53") (pin "2") (pinfunction "2_2") (pintype "passive"))
      (node (ref "U1") (pin "87") (pinfunction "PD6_87") (pintype "bidirectional"))
    )
    (net (code "15") (name "EPHY_NRST") (class "Default")
      (node (ref "U1") (pin "97") (pinfunction "PE0_97") (pintype "bidirectional"))
      (node (ref "U3") (pin "24") (pinfunction "RST#_24") (pintype "input"))
    )
    (net (code "16") (name "ETH_CRS_DV") (class "Default")
      (node (ref "R64") (pin "2") (pinfunction "2_2") (pintype "passive"))
      (node (ref "U1") (pin "32") (pinfunction "PA7/ETH_MII_RX_DV_32") (pintype "bidirectional"))
    )
    (net (code "17") (name "ETH_MDC") (class "Default")
      (node (ref "R65") (pin "2") (pinfunction "2_2") (pintype "passive"))
      (node (ref "U3") (pin "11") (pinfunction "MDC_11") (pintype "input"))
    )
    (net (code "18") (name "ETH_MDINT") (class "Default")
      (node (ref "R56") (pin "2") (pinfunction "2_2") (pintype "passive"))
      (node (ref "R63") (pin "2") (pinfunction "2_2") (pintype "passive"))
      (node (ref "U1") (pin "26") (pinfunction "PA3/ETH_MII_COL_26") (pintype "bidirectional"))
    )
    (net (code "19") (name "ETH_MDIO") (class "Default")
      (node (ref "R55") (pin "2") (pinfunction "2_2") (pintype "passive"))
      (node (ref "R66") (pin "2") (pinfunction "2_2") (pintype "passive"))
      (node (ref "R67") (pin "2") (pinfunction "2_2") (pintype "passive"))
    )
    (net (code "20") (name "ETH_RMII_REF_CLK") (class "Default")
      (node (ref "R62") (pin "2") (pinfunction "2_2") (pintype "passive"))
      (node (ref "U1") (pin "24") (pinfunction "PA1/ETH_MII_RX_CLK_24") (pintype "bidirectional"))
    )
    (net (code "21") (name "ETH_RXD0") (class "Default")
      (node (ref "R35") (pin "2") (pinfunction "2_2") (pintype "passive"))
      (node (ref "U1") (pin "33") (pinfunction "PC4/ETH_MII_RXD0_33") (pintype "bidirectional"))
    )
    (net (code "22") (name "ETH_RXD1") (class "Default")
      (node (ref "R34") (pin "2") (pinfunction "2_2") (pintype "passive"))
      (node (ref "U1") (pin "34") (pinfunction "PC5/ETH_MII_RXD1_34") (pintype "bidirectional"))
    )
    (net (code "23") (name "ETH_TXD0") (class "Default")
      (node (ref "R58") (pin "2") (pinfunction "2_2") (pintype "passive"))
      (node (ref "U3") (pin "20") (pinfunction "TXD0_20") (pintype "input"))
    )
    (net (code "24") (name "ETH_TXD1") (class "Default")
      (node (ref "R61") (pin "2") (pinfunction "2_2") (pintype "passive"))
      (node (ref "U3") (pin "21") (pinfunction "TXD1_21") (pintype "input"))
    )
    (net (code "25") (name "ETH_TX_EN") (class "Default")
      (node (ref "R57") (pin "2") (pinfunction "2_2") (pintype "passive"))
      (node (ref "U3") (pin "19") (pinfunction "TXEN_19") (pintype "input"))
    )
    (net (code "26") (name "GND") (class "Default")
      (node (ref "ADC1") (pin "4") (pinfunction "IN-_4") (pintype "input"))
      (node (ref "ADC1") (pin "5") (pinfunction "GND_5") (pintype "power_in"))
      (node (ref "ADC2") (pin "4") (pinfunction "IN-_4") (pintype "input"))
      (node (ref "ADC2") (pin "5") (pinfunction "GND_5") (pintype "power_in"))
      (node (ref "ADC3") (pin "4") (pinfunction "IN-_4") (pintype "input"))
      (node (ref "ADC3") (pin "5") (pinfunction "GND_5") (pintype "power_in"))
      (node (ref "ADC4") (pin "4") (pinfunction "IN-_4") (pintype "input"))
      (node (ref "ADC4") (pin "5") (pinfunction "GND_5") (pintype "power_in"))
      (node (ref "C1") (pin "1") (pinfunction "1_1") (pintype "passive"))
      (node (ref "C10") (pin "2") (pinfunction "2_2") (pintype "passive"))
      (node (ref "C101") (pin "2") (pinfunction "2_2") (pintype "passive"))
      (node (ref "C102") (pin "2") (pinfunction "2_2") (pintype "passive"))
      (node (ref "C103") (pin "2") (pinfunction "2_2") (pintype "passive"))
      (node (ref "C104") (pin "2") (pinfunction "2_2") (pintype "passive"))
      (node (ref "C109") (pin "2") (pinfunction "2_2") (pintype "passive"))
      (node (ref "C110") (pin "2") (pinfunction "2_2") (pintype "passive"))
      (node (ref "C111") (pin "2") (pinfunction "2_2") (pintype "passive"))
      (node (ref "C112") (pin "2") (pinfunction "2_2") (pintype "passive"))
      (node (ref "C117") (pin "2") (pinfunction "2_2") (pintype "passive"))
      (node (ref "C118") (pin "2") (pinfunction "2_2") (pintype "passive"))
      (node (ref "C119") (pin "2") (pinfunction "2_2") (pintype "passive"))
      (node (ref "C12") (pin "2") (pinfunction "2_2") (pintype "passive"))
      (node (ref "C120") (pin "2") (pinfunction "2_2") (pintype "passive"))
      (node (ref "C125") (pin "-") (pinfunction "-_-") (pintype "passive"))
      (node (ref "C126") (pin "2") (pinfunction "2_2") (pintype "passive"))
      (node (ref "C127") (pin "2") (pinfunction "2_2") (pintype "passive"))
      (node (ref "C128") (pin "2") (pinfunction "2_2") (pintype "passive"))
      (node (ref "C13") (pin "2") (pinfunction "2_2") (pintype "passive"))
      (node (ref "C131") (pin "2") (pinfunction "2_2") (pintype "passive"))
      (node (ref "C132") (pin "2") (pinfunction "2_2") (pintype "passive"))
      (node (ref "C14") (pin "2") (pinfunction "2_2") (pintype "passive"))
      (node (ref "C16") (pin "2") (pinfunction "2_2") (pintype "passive"))
      (node (ref "C17") (pin "2") (pinfunction "2_2") (pintype "passive"))
      (node (ref "C18") (pin "2") (pinfunction "2_2") (pintype "passive"))
      (node (ref "C2") (pin "1") (pinfunction "1_1") (pintype "passive"))
      (node (ref "C20") (pin "2") (pinfunction "2_2") (pintype "passive"))
      (node (ref "C21") (pin "2") (pinfunction "2_2") (pintype "passive"))
      (node (ref "C22") (pin "2") (pinfunction "2_2") (pintype "passive"))
      (node (ref "C23") (pin "2") (pinfunction "2_2") (pintype "passive"))
      (node (ref "C24") (pin "2") (pinfunction "2_2") (pintype "passive"))
      (node (ref "C25") (pin "2") (pinfunction "2_2") (pintype "passive"))
      (node (ref "C26") (pin "2") (pinfunction "2_2") (pintype "passive"))
      (node (ref "C27") (pin "2") (pinfunction "2_2") (pintype "passive"))
      (node (ref "C28") (pin "2") (pinfunction "2_2") (pintype "passive"))
      (node (ref "C29") (pin "2") (pinfunction "2_2") (pintype "passive"))
      (node (ref "C3") (pin "1") (pinfunction "1_1") (pintype "passive"))
      (node (ref "C30") (pin "-") (pinfunction "-_-") (pintype "passive"))
      (node (ref "C31") (pin "2") (pinfunction "2_2") (pintype "passive"))
      (node (ref "C33") (pin "1") (pinfunction "1_1") (pintype "passive"))
      (node (ref "C34") (pin "-") (pinfunction "-_-") (pintype "passive"))
      (node (ref "C35") (pin "-") (pinfunction "-_-") (pintype "passive"))
      (node (ref "C36") (pin "2") (pinfunction "2_2") (pintype "passive"))
      (node (ref "C38") (pin "2") (pinfunction "2_2") (pintype "passive"))
      (node (ref "C39") (pin "2") (pinfunction "2_2") (pintype "passive"))
      (node (ref "C4") (pin "2") (pinfunction "2_2") (pintype "passive"))
      (node (ref "C40") (pin "1") (pinfunction "1_1") (pintype "passive"))
      (node (ref "C41") (pin "2") (pinfunction "2_2") (pintype "passive"))
      (node (ref "C42") (pin "2") (pinfunction "2_2") (pintype "passive"))
      (node (ref "C43") (pin "2") (pinfunction "2_2") (pintype "passive"))
      (node (ref "C45") (pin "2") (pinfunction "2_2") (pintype "passive"))
      (node (ref "C46") (pin "2") (pinfunction "2_2") (pintype "passive"))
      (node (ref "C47") (pin "-") (pinfunction "-_-") (pintype "passive"))
      (node (ref "C49") (pin "2") (pinfunction "2_2") (pintype "passive"))
      (node (ref "C5") (pin "2") (pinfunction "2_2") (pintype "passive"))
      (node (ref "C50") (pin "-") (pinfunction "-_-") (pintype "passive"))
      (node (ref "C54") (pin "1") (pinfunction "1_1") (pintype "passive"))
      (node (ref "C55") (pin "2") (pinfunction "2_2") (pintype "passive"))
      (node (ref "C6") (pin "2") (pinfunction "2_2") (pintype "passive"))
      (node (ref "C7") (pin "2") (pinfunction "2_2") (pintype "passive"))
      (node (ref "C72") (pin "2") (pinfunction "2_2") (pintype "passive"))
      (node (ref "C73") (pin "1") (pinfunction "1_1") (pintype "passive"))
      (node (ref "C75") (pin "1") (pinfunction "1_1") (pintype "passive"))
      (node (ref "C76") (pin "2") (pinfunction "2_2") (pintype "passive"))
      (node (ref "C77") (pin "2") (pinfunction "2_2") (pintype "passive"))
      (node (ref "C78") (pin "2") (pinfunction "2_2") (pintype "passive"))
      (node (ref "C79") (pin "2") (pinfunction "2_2") (pintype "passive"))
      (node (ref "C8") (pin "2") (pinfunction "2_2") (pintype "passive"))
      (node (ref "C80") (pin "2") (pinfunction "2_2") (pintype "passive"))
      (node (ref "C81") (pin "2") (pinfunction "2_2") (pintype "passive"))
      (node (ref "C82") (pin "2") (pinfunction "2_2") (pintype "passive"))
      (node (ref "C83") (pin "2") (pinfunction "2_2") (pintype "passive"))
      (node (ref "C84") (pin "2") (pinfunction "2_2") (pintype "passive"))
      (node (ref "C85") (pin "2") (pinfunction "2_2") (pintype "passive"))
      (node (ref "C86") (pin "2") (pinfunction "2_2") (pintype "passive"))
      (node (ref "C87") (pin "2") (pinfunction "2_2") (pintype "passive"))
      (node (ref "C88") (pin "2") (pinfunction "2_2") (pintype "passive"))
      (node (ref "C89") (pin "2") (pinfunction "2_2") (pintype "passive"))
      (node (ref "C9") (pin "2") (pinfunction "2_2") (pintype "passive"))
      (node (ref "C90") (pin "2") (pinfunction "2_2") (pintype "passive"))
      (node (ref "C91") (pin "2") (pinfunction "2_2") (pintype "passive"))
      (node (ref "C92") (pin "2") (pinfunction "2_2") (pintype "passive"))
      (node (ref "C93") (pin "2") (pinfunction "2_2") (pintype "passive"))
      (node (ref "C94") (pin "2") (pinfunction "2_2") (pintype "passive"))
      (node (ref "C95") (pin "2") (pinfunction "2_2") (pintype "passive"))
      (node (ref "C96") (pin "2") (pinfunction "2_2") (pintype "passive"))
      (node (ref "C97") (pin "1") (pinfunction "1_1") (pintype "passive"))
      (node (ref "C98") (pin "1") (pinfunction "1_1") (pintype "passive"))
      (node (ref "C99") (pin "1") (pinfunction "1_1") (pintype "passive"))
      (node (ref "GND") (pin "P$1") (pinfunction "P$1_P$1") (pintype "bidirectional"))
      (node (ref "J22") (pin "GND") (pinfunction "GND_GND") (pintype "passive"))
      (node (ref "J22") (pin "GND@2") (pinfunction "GND_GND@2") (pintype "passive"))
      (node (ref "J22") (pin "GNDDET") (pinfunction "GNDDET_GNDDET") (pintype "passive"))
      (node (ref "JP1") (pin "1") (pinfunction "1_1") (pintype "passive"))
      (node (ref "JP1") (pin "2") (pinfunction "2_2") (pintype "passive"))
      (node (ref "JP2") (pin "5") (pinfunction "5_5") (pintype "passive"))
      (node (ref "JP2") (pin "6") (pinfunction "6_6") (pintype "passive"))
      (node (ref "JP3") (pin "1") (pinfunction "1_1") (pintype "passive"))
      (node (ref "JP3") (pin "2") (pinfunction "2_2") (pintype "passive"))
      (node (ref "JP4") (pin "5") (pinfunction "5_5") (pintype "passive"))
      (node (ref "JP4") (pin "6") (pinfunction "6_6") (pintype "passive"))
      (node (ref "JP5") (pin "5") (pinfunction "5_5") (pintype "passive"))
      (node (ref "JP5") (pin "6") (pinfunction "6_6") (pintype "passive"))
      (node (ref "JP6") (pin "1") (pinfunction "1_1") (pintype "passive"))
      (node (ref "JP6") (pin "2") (pinfunction "2_2") (pintype "passive"))
      (node (ref "OPAMP1") (pin "4") (pinfunction "V-_4") (pintype "power_in"))
      (node (ref "OPAMP2") (pin "4") (pinfunction "V-_4") (pintype "power_in"))
      (node (ref "POE") (pin "3") (pinfunction "CASE_3") (pintype "input"))
      (node (ref "POE") (pin "4") (pinfunction "-VIN_4") (pintype "power_in"))
      (node (ref "R14") (pin "1") (pinfunction "1_1") (pintype "passive"))
      (node (ref "R15") (pin "1") (pinfunction "1_1") (pintype "passive"))
      (node (ref "R16") (pin "1") (pinfunction "1_1") (pintype "passive"))
      (node (ref "R38") (pin "2") (pinfunction "2_2") (pintype "passive"))
      (node (ref "R60") (pin "1") (pinfunction "1_1") (pintype "passive"))
      (node (ref "REF1") (pin "4") (pinfunction "GND_4") (pintype "bidirectional"))
      (node (ref "SW1") (pin "2") (pinfunction "2_2") (pintype "bidirectional"))
      (node (ref "SW1") (pin "4") (pinfunction "4_4") (pintype "bidirectional"))
      (node (ref "U1") (pin "10") (pinfunction "VSS_10") (pintype "power_in"))
      (node (ref "U1") (pin "20") (pinfunction "VSSA_20") (pintype "power_in"))
      (node (ref "U1") (pin "27") (pinfunction "VSS_27") (pintype "power_in"))
      (node (ref "U1") (pin "74") (pinfunction "VSS_74") (pintype "power_in"))
      (node (ref "U1") (pin "99") (pinfunction "VSS_99") (pintype "power_in"))
      (node (ref "U3") (pin "22") (pinfunction "GND_22") (pintype "power_in"))
      (node (ref "U3") (pin "PAD") (pinfunction "PAD_GND_PAD") (pintype "power_in"))
      (node (ref "VR2") (pin "4") (pinfunction "GND_4") (pintype "bidirectional"))
      (node (ref "VR2") (pin "PAD") (pinfunction "GND_PAD") (pintype "bidirectional"))
      (node (ref "VR3") (pin "1") (pinfunction "~{EN}_1") (pintype "bidirectional"))
      (node (ref "VR3") (pin "3") (pinfunction "GND_3") (pintype "bidirectional"))
      (node (ref "VR6") (pin "1") (pinfunction "ADJ/GND_1") (pintype "power_in"))
      (node (ref "VR8") (pin "3") (pinfunction "GND_3") (pintype "power_in"))
      (node (ref "X4") (pin "5") (pinfunction "5_5") (pintype "passive"))
    )
    (net (code "27") (name "JTAG_TCK") (class "Default")
      (node (ref "J22") (pin "TCK") (pinfunction "TCK_TCK") (pintype "passive"))
      (node (ref "U1") (pin "76") (pinfunction "PA14/JTCK_76") (pintype "bidirectional"))
    )
    (net (code "28") (name "JTAG_TDI") (class "Default")
      (node (ref "J22") (pin "TDI") (pinfunction "TDI_TDI") (pintype "passive"))
      (node (ref "U1") (pin "77") (pinfunction "PA15/JTDI_77") (pintype "bidirectional"))
    )
    (net (code "29") (name "JTAG_TDO") (class "Default")
      (node (ref "J22") (pin "TDO") (pinfunction "TDO_TDO") (pintype "passive"))
      (node (ref "U1") (pin "89") (pinfunction "PB3/JTDO_89") (pintype "bidirectional"))
    )
    (net (code "30") (name "JTAG_TMS") (class "Default")
      (node (ref "J22") (pin "TMS") (pinfunction "TMS_TMS") (pintype "passive"))
      (node (ref "U1") (pin "72") (pinfunction "PA13/JTMS_72") (pintype "bidirectional"))
    )
    (net (code "31") (name "MCO1-ETH-CLK") (class "Default")
      (node (ref "R68") (pin "2") (pinfunction "2_2") (pintype "passive"))
      (node (ref "U3") (pin "8") (pinfunction "XI_8") (pintype "input"))
    )
    (net (code "32") (name "NRST") (class "Default")
      (node (ref "C92") (pin "1") (pinfunction "1_1") (pintype "passive"))
      (node (ref "J22") (pin "!RESET") (pinfunction "~{RESET}_!RESET") (pintype "passive"))
      (node (ref "SW1") (pin "1") (pinfunction "1_1") (pintype "bidirectional"))
      (node (ref "SW1") (pin "3") (pinfunction "3_3") (pintype "bidirectional"))
      (node (ref "U1") (pin "14") (pinfunction "NRST_14") (pintype "input"))
    )
    (net (code "33") (name "Net-(ADC1-IN+)") (class "Default")
      (node (ref "ADC1") (pin "3") (pinfunction "IN+_3") (pintype "input"))
      (node (ref "C11") (pin "2") (pinfunction "2_2") (pintype "passive"))
      (node (ref "OPAMP1") (pin "1") (pinfunction "OUT_A_1") (pintype "output"))
      (node (ref "OPAMP1") (pin "2") (pinfunction "-_2") (pintype "input"))
    )
    (net (code "34") (name "Net-(ADC1-SDO)") (class "Default")
      (node (ref "ADC1") (pin "7") (pinfunction "SDO_7") (pintype "output"))
      (node (ref "ADC2") (pin "9") (pinfunction "SDI_9") (pintype "input"))
    )
    (net (code "35") (name "Net-(ADC2-IN+)") (class "Default")
      (node (ref "ADC2") (pin "3") (pinfunction "IN+_3") (pintype "input"))
      (node (ref "C15") (pin "2") (pinfunction "2_2") (pintype "passive"))
      (node (ref "OPAMP1") (pin "6") (pinfunction "-_6") (pintype "bidirectional"))
      (node (ref "OPAMP1") (pin "7") (pinfunction "OUT_B_7") (pintype "bidirectional"))
    )
    (net (code "36") (name "Net-(ADC2-SDO)") (class "Default")
      (node (ref "ADC2") (pin "7") (pinfunction "SDO_7") (pintype "output"))
      (node (ref "ADC3") (pin "9") (pinfunction "SDI_9") (pintype "input"))
    )
    (net (code "37") (name "Net-(ADC3-IN+)") (class "Default")
      (node (ref "ADC3") (pin "3") (pinfunction "IN+_3") (pintype "input"))
      (node (ref "C19") (pin "2") (pinfunction "2_2") (pintype "passive"))
      (node (ref "OPAMP2") (pin "1") (pinfunction "OUT_A_1") (pintype "output"))
      (node (ref "OPAMP2") (pin "2") (pinfunction "-_2") (pintype "input"))
    )
    (net (code "38") (name "Net-(ADC3-SDO)") (class "Default")
      (node (ref "ADC3") (pin "7") (pinfunction "SDO_7") (pintype "output"))
      (node (ref "ADC4") (pin "9") (pinfunction "SDI_9") (pintype "input"))
    )
    (net (code "39") (name "Net-(ADC4-IN+)") (class "Default")
      (node (ref "ADC4") (pin "3") (pinfunction "IN+_3") (pintype "input"))
      (node (ref "C37") (pin "2") (pinfunction "2_2") (pintype "passive"))
      (node (ref "OPAMP2") (pin "6") (pinfunction "-_6") (pintype "bidirectional"))
      (node (ref "OPAMP2") (pin "7") (pinfunction "OUT_B_7") (pintype "bidirectional"))
    )
    (net (code "40") (name "Net-(ADC4-SDO)") (class "Default")
      (node (ref "ADC4") (pin "7") (pinfunction "SDO_7") (pintype "output"))
      (node (ref "R20") (pin "1") (pinfunction "1_1") (pintype "passive"))
    )
    (net (code "41") (name "Net-(C10-Pad1)") (class "Default")
      (node (ref "C10") (pin "1") (pinfunction "1_1") (pintype "passive"))
      (node (ref "R1") (pin "2") (pinfunction "2_2") (pintype "passive"))
      (node (ref "R2") (pin "1") (pinfunction "1_1") (pintype "passive"))
    )
    (net (code "42") (name "Net-(C11-Pad1)") (class "Default")
      (node (ref "C11") (pin "1") (pinfunction "1_1") (pintype "passive"))
      (node (ref "R2") (pin "2") (pinfunction "2_2") (pintype "passive"))
      (node (ref "R3") (pin "1") (pinfunction "1_1") (pintype "passive"))
    )
    (net (code "43") (name "Net-(C14-Pad1)") (class "Default")
      (node (ref "C14") (pin "1") (pinfunction "1_1") (pintype "passive"))
      (node (ref "R4") (pin "2") (pinfunction "2_2") (pintype "passive"))
      (node (ref "R5") (pin "1") (pinfunction "1_1") (pintype "passive"))
    )
    (net (code "44") (name "Net-(C15-Pad1)") (class "Default")
      (node (ref "C15") (pin "1") (pinfunction "1_1") (pintype "passive"))
      (node (ref "R5") (pin "2") (pinfunction "2_2") (pintype "passive"))
      (node (ref "R6") (pin "1") (pinfunction "1_1") (pintype "passive"))
    )
    (net (code "45") (name "Net-(C18-Pad1)") (class "Default")
      (node (ref "C18") (pin "1") (pinfunction "1_1") (pintype "passive"))
      (node (ref "R7") (pin "2") (pinfunction "2_2") (pintype "passive"))
      (node (ref "R8") (pin "1") (pinfunction "1_1") (pintype "passive"))
    )
    (net (code "46") (name "Net-(C19-Pad1)") (class "Default")
      (node (ref "C19") (pin "1") (pinfunction "1_1") (pintype "passive"))
      (node (ref "R8") (pin "2") (pinfunction "2_2") (pintype "passive"))
      (node (ref "R9") (pin "1") (pinfunction "1_1") (pintype "passive"))
    )
    (net (code "47") (name "Net-(C36-Pad1)") (class "Default")
      (node (ref "C36") (pin "1") (pinfunction "1_1") (pintype "passive"))
      (node (ref "R17") (pin "2") (pinfunction "2_2") (pintype "passive"))
      (node (ref "R18") (pin "1") (pinfunction "1_1") (pintype "passive"))
    )
    (net (code "48") (name "Net-(C37-Pad1)") (class "Default")
      (node (ref "C37") (pin "1") (pinfunction "1_1") (pintype "passive"))
      (node (ref "R18") (pin "2") (pinfunction "2_2") (pintype "passive"))
      (node (ref "R19") (pin "1") (pinfunction "1_1") (pintype "passive"))
    )
    (net (code "49") (name "Net-(C93-Pad1)") (class "Default")
      (node (ref "C93") (pin "1") (pinfunction "1_1") (pintype "passive"))
      (node (ref "JP3") (pin "3") (pinfunction "3_3") (pintype "passive"))
      (node (ref "R48") (pin "1") (pinfunction "1_1") (pintype "passive"))
    )
    (net (code "50") (name "Net-(C94-Pad1)") (class "Default")
      (node (ref "C94") (pin "1") (pinfunction "1_1") (pintype "passive"))
      (node (ref "JP3") (pin "4") (pinfunction "4_4") (pintype "passive"))
      (node (ref "R47") (pin "1") (pinfunction "1_1") (pintype "passive"))
    )
    (net (code "51") (name "Net-(C95-Pad1)") (class "Default")
      (node (ref "C95") (pin "1") (pinfunction "1_1") (pintype "passive"))
      (node (ref "JP3") (pin "5") (pinfunction "5_5") (pintype "passive"))
      (node (ref "R46") (pin "1") (pinfunction "1_1") (pintype "passive"))
    )
    (net (code "52") (name "Net-(C96-Pad1)") (class "Default")
      (node (ref "C96") (pin "1") (pinfunction "1_1") (pintype "passive"))
      (node (ref "JP3") (pin "6") (pinfunction "6_6") (pintype "passive"))
      (node (ref "R45") (pin "1") (pinfunction "1_1") (pintype "passive"))
    )
    (net (code "53") (name "Net-(C101-Pad1)") (class "Default")
      (node (ref "C101") (pin "1") (pinfunction "1_1") (pintype "passive"))
      (node (ref "JP4") (pin "1") (pinfunction "1_1") (pintype "passive"))
      (node (ref "R53") (pin "1") (pinfunction "1_1") (pintype "passive"))
    )
    (net (code "54") (name "Net-(C102-Pad1)") (class "Default")
      (node (ref "C102") (pin "1") (pinfunction "1_1") (pintype "passive"))
      (node (ref "JP4") (pin "2") (pinfunction "2_2") (pintype "passive"))
      (node (ref "R52") (pin "1") (pinfunction "1_1") (pintype "passive"))
    )
    (net (code "55") (name "Net-(C103-Pad1)") (class "Default")
      (node (ref "C103") (pin "1") (pinfunction "1_1") (pintype "passive"))
      (node (ref "JP4") (pin "3") (pinfunction "3_3") (pintype "passive"))
      (node (ref "R51") (pin "1") (pinfunction "1_1") (pintype "passive"))
    )
    (net (code "56") (name "Net-(C104-Pad1)") (class "Default")
      (node (ref "C104") (pin "1") (pinfunction "1_1") (pintype "passive"))
      (node (ref "JP4") (pin "4") (pinfunction "4_4") (pintype "passive"))
      (node (ref "R49") (pin "1") (pinfunction "1_1") (pintype "passive"))
    )
    (net (code "57") (name "Net-(C109-Pad1)") (class "Default")
      (node (ref "C109") (pin "1") (pinfunction "1_1") (pintype "passive"))
      (node (ref "JP2") (pin "1") (pinfunction "1_1") (pintype "passive"))
      (node (ref "R44") (pin "1") (pinfunction "1_1") (pintype "passive"))
    )
    (net (code "58") (name "Net-(C110-Pad1)") (class "Default")
      (node (ref "C110") (pin "1") (pinfunction "1_1") (pintype "passive"))
      (node (ref "JP2") (pin "2") (pinfunction "2_2") (pintype "passive"))
      (node (ref "R43") (pin "1") (pinfunction "1_1") (pintype "passive"))
    )
    (net (code "59") (name "Net-(C111-Pad1)") (class "Default")
      (node (ref "C111") (pin "1") (pinfunction "1_1") (pintype "passive"))
      (node (ref "JP2") (pin "3") (pinfunction "3_3") (pintype "passive"))
      (node (ref "R42") (pin "1") (pinfunction "1_1") (pintype "passive"))
    )
    (net (code "60") (name "Net-(C112-Pad1)") (class "Default")
      (node (ref "C112") (pin "1") (pinfunction "1_1") (pintype "passive"))
      (node (ref "JP2") (pin "4") (pinfunction "4_4") (pintype "passive"))
      (node (ref "R41") (pin "1") (pinfunction "1_1") (pintype "passive"))
    )
    (net (code "61") (name "Net-(C117-Pad1)") (class "Default")
      (node (ref "C117") (pin "1") (pinfunction "1_1") (pintype "passive"))
      (node (ref "JP1") (pin "6") (pinfunction "6_6") (pintype "passive"))
      (node (ref "R40") (pin "1") (pinfunction "1_1") (pintype "passive"))
    )
    (net (code "62") (name "Net-(C118-Pad1)") (class "Default")
      (node (ref "C118") (pin "1") (pinfunction "1_1") (pintype "passive"))
      (node (ref "JP1") (pin "5") (pinfunction "5_5") (pintype "passive"))
      (node (ref "R39") (pin "1") (pinfunction "1_1") (pintype "passive"))
    )
    (net (code "63") (name "Net-(C119-Pad1)") (class "Default")
      (node (ref "C119") (pin "1") (pinfunction "1_1") (pintype "passive"))
      (node (ref "JP1") (pin "4") (pinfunction "4_4") (pintype "passive"))
      (node (ref "R37") (pin "1") (pinfunction "1_1") (pintype "passive"))
    )
    (net (code "64") (name "Net-(C120-Pad1)") (class "Default")
      (node (ref "C120") (pin "1") (pinfunction "1_1") (pintype "passive"))
      (node (ref "JP1") (pin "3") (pinfunction "3_3") (pintype "passive"))
      (node (ref "R50") (pin "1") (pinfunction "1_1") (pintype "passive"))
    )
    (net (code "65") (name "Net-(D5-C)") (class "Default")
      (node (ref "D5") (pin "P$2") (pinfunction "C_P$2") (pintype "passive"))
      (node (ref "IC2") (pin "23") (pinfunction "DET_23") (pintype "bidirectional"))
    )
    (net (code "66") (name "Net-(IC2-EN)") (class "Default")
      (node (ref "C44") (pin "1") (pinfunction "1_1") (pintype "passive"))
      (node (ref "IC2") (pin "14") (pinfunction "EN_14") (pintype "bidirectional"))
    )
    (net (code "67") (name "Net-(IC2-ILIM1)") (class "Default")
      (node (ref "IC2") (pin "4") (pinfunction "ILIM1_4") (pintype "bidirectional"))
      (node (ref "R23") (pin "1") (pinfunction "1_1") (pintype "passive"))
    )
    (net (code "68") (name "Net-(IC2-ILIM2)") (class "Default")
      (node (ref "IC2") (pin "5") (pinfunction "ILIM2_5") (pintype "bidirectional"))
      (node (ref "R24") (pin "1") (pinfunction "1_1") (pintype "passive"))
    )
    (net (code "69") (name "Net-(IC2-LED)") (class "Default")
      (node (ref "IC2") (pin "17") (pinfunction "LED_17") (pintype "bidirectional"))
      (node (ref "R_LED") (pin "1") (pinfunction "1_1") (pintype "passive"))
    )
    (net (code "70") (name "Net-(JP5-Pad3)") (class "Default")
      (node (ref "JP5") (pin "3") (pinfunction "3_3") (pintype "passive"))
      (node (ref "R4") (pin "1") (pinfunction "1_1") (pintype "passive"))
    )
    (net (code "71") (name "Net-(JP5-Pad4)") (class "Default")
      (node (ref "JP5") (pin "4") (pinfunction "4_4") (pintype "passive"))
      (node (ref "R1") (pin "1") (pinfunction "1_1") (pintype "passive"))
    )
    (net (code "72") (name "Net-(JP6-Pad3)") (class "Default")
      (node (ref "JP6") (pin "3") (pinfunction "3_3") (pintype "passive"))
      (node (ref "R17") (pin "1") (pinfunction "1_1") (pintype "passive"))
    )
    (net (code "73") (name "Net-(JP6-Pad4)") (class "Default")
      (node (ref "JP6") (pin "4") (pinfunction "4_4") (pintype "passive"))
      (node (ref "R7") (pin "1") (pinfunction "1_1") (pintype "passive"))
    )
    (net (code "74") (name "Net-(LED1A-A)") (class "Default")
      (node (ref "LED1") (pin "4") (pinfunction "A_4") (pintype "passive"))
      (node (ref "R25") (pin "2") (pinfunction "2_2") (pintype "passive"))
    )
    (net (code "75") (name "Net-(LED1A-K)") (class "Default")
      (node (ref "LED1") (pin "5") (pinfunction "K_5") (pintype "passive"))
      (node (ref "U1") (pin "42") (pinfunction "PE11_42") (pintype "bidirectional"))
    )
    (net (code "76") (name "Net-(LED1B-A)") (class "Default")
      (node (ref "LED1") (pin "3") (pinfunction "A_3") (pintype "passive"))
      (node (ref "R26") (pin "2") (pinfunction "2_2") (pintype "passive"))
    )
    (net (code "77") (name "Net-(LED1B-K)") (class "Default")
      (node (ref "LED1") (pin "2") (pinfunction "K_2") (pintype "passive"))
      (node (ref "U1") (pin "40") (pinfunction "PE9_40") (pintype "bidirectional"))
    )
    (net (code "78") (name "Net-(LED1D-A)") (class "Default")
      (node (ref "LED1") (pin "1") (pinfunction "A_1") (pintype "passive"))
      (node (ref "R27") (pin "2") (pinfunction "2_2") (pintype "passive"))
    )
    (net (code "79") (name "Net-(LED1D-K)") (class "Default")
      (node (ref "LED1") (pin "6") (pinfunction "K_6") (pintype "passive"))
      (node (ref "U1") (pin "44") (pinfunction "PE13_44") (pintype "bidirectional"))
    )
    (net (code "80") (name "Net-(LED2-PadA)") (class "Default")
      (node (ref "LED2") (pin "A") (pinfunction "A_A") (pintype "passive"))
      (node (ref "R28") (pin "2") (pinfunction "2_2") (pintype "passive"))
    )
    (net (code "81") (name "Net-(LED3-PadA)") (class "Default")
      (node (ref "LED3") (pin "A") (pinfunction "A_A") (pintype "passive"))
      (node (ref "R29") (pin "2") (pinfunction "2_2") (pintype "passive"))
    )
    (net (code "82") (name "Net-(LED4-PadA)") (class "Default")
      (node (ref "LED4") (pin "A") (pinfunction "A_A") (pintype "passive"))
      (node (ref "R30") (pin "2") (pinfunction "2_2") (pintype "passive"))
    )
    (net (code "83") (name "Net-(LED5-PadA)") (class "Default")
      (node (ref "LED5") (pin "A") (pinfunction "A_A") (pintype "passive"))
      (node (ref "R31") (pin "2") (pinfunction "2_2") (pintype "passive"))
    )
    (net (code "84") (name "Net-(OPAMP1A-+)") (class "Default")
      (node (ref "C12") (pin "1") (pinfunction "1_1") (pintype "passive"))
      (node (ref "C13") (pin "1") (pinfunction "1_1") (pintype "passive"))
      (node (ref "OPAMP1") (pin "3") (pinfunction "+_3") (pintype "input"))
      (node (ref "R3") (pin "2") (pinfunction "2_2") (pintype "passive"))
    )
    (net (code "85") (name "Net-(OPAMP1B-+)") (class "Default")
      (node (ref "C16") (pin "1") (pinfunction "1_1") (pintype "passive"))
      (node (ref "C17") (pin "1") (pinfunction "1_1") (pintype "passive"))
      (node (ref "OPAMP1") (pin "5") (pinfunction "+_5") (pintype "bidirectional"))
      (node (ref "R6") (pin "2") (pinfunction "2_2") (pintype "passive"))
    )
    (net (code "86") (name "Net-(OPAMP2A-+)") (class "Default")
      (node (ref "C20") (pin "1") (pinfunction "1_1") (pintype "passive"))
      (node (ref "C21") (pin "1") (pinfunction "1_1") (pintype "passive"))
      (node (ref "OPAMP2") (pin "3") (pinfunction "+_3") (pintype "input"))
      (node (ref "R9") (pin "2") (pinfunction "2_2") (pintype "passive"))
    )
    (net (code "87") (name "Net-(OPAMP2B-+)") (class "Default")
      (node (ref "C38") (pin "1") (pinfunction "1_1") (pintype "passive"))
      (node (ref "C39") (pin "1") (pinfunction "1_1") (pintype "passive"))
      (node (ref "OPAMP2") (pin "5") (pinfunction "+_5") (pintype "bidirectional"))
      (node (ref "R19") (pin "2") (pinfunction "2_2") (pintype "passive"))
    )
    (net (code "88") (name "Net-(POE-+SENSE)") (class "Default")
      (node (ref "POE") (pin "8") (pinfunction "+SENSE_8") (pintype "bidirectional"))
      (node (ref "R54") (pin "3") (pinfunction "E_3") (pintype "passive"))
    )
    (net (code "89") (name "Net-(POE--SENSE)") (class "Default")
      (node (ref "POE") (pin "6") (pinfunction "-SENSE_6") (pintype "bidirectional"))
      (node (ref "R54") (pin "1") (pinfunction "A_1") (pintype "passive"))
    )
    (net (code "90") (name "Net-(POE-TRIM)") (class "Default")
      (node (ref "POE") (pin "7") (pinfunction "TRIM_7") (pintype "bidirectional"))
      (node (ref "R54") (pin "2") (pinfunction "S_2") (pintype "passive"))
    )
    (net (code "91") (name "Net-(U1A-PA0{slash}ETH_MII_CRS)") (class "Default")
      (node (ref "TP7") (pin "TP") (pinfunction "TP_TP") (pintype "input"))
      (node (ref "U1") (pin "23") (pinfunction "PA0/ETH_MII_CRS_23") (pintype "bidirectional"))
    )
    (net (code "92") (name "Net-(U1A-PA2{slash}ETH_MDIO)") (class "Default")
      (node (ref "R66") (pin "1") (pinfunction "1_1") (pintype "passive"))
      (node (ref "U1") (pin "25") (pinfunction "PA2/ETH_MDIO_25") (pintype "bidirectional"))
    )
    (net (code "93") (name "Net-(U1A-PA4{slash}SPI_NSS)") (class "Default")
      (node (ref "R33") (pin "2") (pinfunction "2_2") (pintype "passive"))
      (node (ref "U1") (pin "29") (pinfunction "PA4/SPI_NSS_29") (pintype "bidirectional"))
    )
    (net (code "94") (name "Net-(U1A-PA5{slash}SPI_SCK)") (class "Default")
      (node (ref "R32") (pin "2") (pinfunction "2_2") (pintype "passive"))
      (node (ref "U1") (pin "30") (pinfunction "PA5/SPI_SCK_30") (pintype "bidirectional"))
    )
    (net (code "95") (name "Net-(U1A-PA8{slash}MCO1)") (class "Default")
      (node (ref "R68") (pin "1") (pinfunction "1_1") (pintype "passive"))
      (node (ref "U1") (pin "67") (pinfunction "PA8/MCO1_67") (pintype "bidirectional"))
    )
    (net (code "96") (name "Net-(U1A-PB11{slash}ETH_MII_TX_EN)") (class "Default")
      (node (ref "R57") (pin "1") (pinfunction "1_1") (pintype "passive"))
      (node (ref "U1") (pin "48") (pinfunction "PB11/ETH_MII_TX_EN_48") (pintype "bidirectional"))
    )
    (net (code "97") (name "Net-(U1A-PB12{slash}ETH_MII_TXD0)") (class "Default")
      (node (ref "R58") (pin "1") (pinfunction "1_1") (pintype "passive"))
      (node (ref "U1") (pin "51") (pinfunction "PB12/ETH_MII_TXD0_51") (pintype "bidirectional"))
    )
    (net (code "98") (name "Net-(U1A-PB13{slash}ETH_MII_TXD1)") (class "Default")
      (node (ref "R61") (pin "1") (pinfunction "1_1") (pintype "passive"))
      (node (ref "U1") (pin "52") (pinfunction "PB13/ETH_MII_TXD1_52") (pintype "bidirectional"))
    )
    (net (code "99") (name "Net-(U1A-PB14)") (class "Default")
      (node (ref "TP6") (pin "TP") (pinfunction "TP_TP") (pintype "input"))
      (node (ref "U1") (pin "53") (pinfunction "PB14_53") (pintype "bidirectional"))
    )
    (net (code "100") (name "Net-(U1A-PC1{slash}ETH_MDC)") (class "Default")
      (node (ref "R65") (pin "1") (pinfunction "1_1") (pintype "passive"))
      (node (ref "U1") (pin "16") (pinfunction "PC1/ETH_MDC_16") (pintype "bidirectional"))
    )
    (net (code "101") (name "Net-(U1A-PC12)") (class "Default")
      (node (ref "TP3") (pin "TP") (pinfunction "TP_TP") (pintype "input"))
      (node (ref "U1") (pin "80") (pinfunction "PC12_80") (pintype "bidirectional"))
    )
    (net (code "102") (name "Net-(U1A-PC14)") (class "Default")
      (node (ref "TP4") (pin "TP") (pinfunction "TP_TP") (pintype "input"))
      (node (ref "U1") (pin "8") (pinfunction "PC14_8") (pintype "bidirectional"))
    )
    (net (code "103") (name "Net-(U1A-PE1)") (class "Default")
      (node (ref "LED2") (pin "C") (pinfunction "C_C") (pintype "passive"))
      (node (ref "U1") (pin "98") (pinfunction "PE1_98") (pintype "bidirectional"))
    )
    (net (code "104") (name "Net-(U1A-PE2)") (class "Default")
      (node (ref "TP1") (pin "TP") (pinfunction "TP_TP") (pintype "input"))
      (node (ref "U1") (pin "1") (pinfunction "PE2_1") (pintype "bidirectional"))
    )
    (net (code "105") (name "Net-(U1A-PE3)") (class "Default")
      (node (ref "LED3") (pin "C") (pinfunction "C_C") (pintype "passive"))
      (node (ref "U1") (pin "2") (pinfunction "PE3_2") (pintype "bidirectional"))
    )
    (net (code "106") (name "Net-(U1A-PE4)") (class "Default")
      (node (ref "TP2") (pin "TP") (pinfunction "TP_TP") (pintype "input"))
      (node (ref "U1") (pin "3") (pinfunction "PE4_3") (pintype "bidirectional"))
    )
    (net (code "107") (name "Net-(U1A-PE5)") (class "Default")
      (node (ref "LED4") (pin "C") (pinfunction "C_C") (pintype "passive"))
      (node (ref "U1") (pin "4") (pinfunction "PE5_4") (pintype "bidirectional"))
    )
    (net (code "108") (name "Net-(U1A-PE6)") (class "Default")
      (node (ref "LED5") (pin "C") (pinfunction "C_C") (pintype "passive"))
      (node (ref "U1") (pin "5") (pinfunction "PE6_5") (pintype "bidirectional"))
    )
    (net (code "109") (name "Net-(U1A-PE10)") (class "Default")
      (node (ref "TP5") (pin "TP") (pinfunction "TP_TP") (pintype "input"))
      (node (ref "U1") (pin "41") (pinfunction "PE10_41") (pintype "bidirectional"))
    )
    (net (code "110") (name "Net-(U1B-BOOT0)") (class "Default")
      (node (ref "R38") (pin "1") (pinfunction "1_1") (pintype "passive"))
      (node (ref "U1") (pin "94") (pinfunction "BOOT0_94") (pintype "input"))
    )
    (net (code "111") (name "Net-(U1B-VBAT)") (class "Default")
      (node (ref "R36") (pin "2") (pinfunction "2_2") (pintype "passive"))
      (node (ref "U1") (pin "6") (pinfunction "VBAT_6") (pintype "power_in"))
    )
    (net (code "112") (name "Net-(U1B-VCAP_1)") (class "Default")
      (node (ref "C87") (pin "1") (pinfunction "1_1") (pintype "passive"))
      (node (ref "U1") (pin "49") (pinfunction "VCAP_1_49") (pintype "power_in"))
    )
    (net (code "113") (name "Net-(U1B-VCAP_2)") (class "Default")
      (node (ref "C86") (pin "1") (pinfunction "1_1") (pintype "passive"))
      (node (ref "U1") (pin "73") (pinfunction "VCAP_2_73") (pintype "power_in"))
    )
    (net (code "114") (name "Net-(U3-CRS_DV{slash}PHYADD)") (class "Default")
      (node (ref "R64") (pin "1") (pinfunction "1_1") (pintype "passive"))
      (node (ref "U3") (pin "15") (pinfunction "CRS_DV/PHYADD_15") (pintype "output"))
    )
    (net (code "115") (name "Net-(U3-INTRP)") (class "Default")
      (node (ref "R63") (pin "1") (pinfunction "1_1") (pintype "passive"))
      (node (ref "U3") (pin "18") (pinfunction "INTRP_18") (pintype "output"))
    )
    (net (code "116") (name "Net-(U3-MDIO)") (class "Default")
      (node (ref "R67") (pin "1") (pinfunction "1_1") (pintype "passive"))
      (node (ref "U3") (pin "10") (pinfunction "MDIO_10") (pintype "bidirectional"))
    )
    (net (code "117") (name "Net-(U3-REF_CLK)") (class "Default")
      (node (ref "R62") (pin "1") (pinfunction "1_1") (pintype "passive"))
      (node (ref "U3") (pin "16") (pinfunction "REF_CLK_16") (pintype "output"))
    )
    (net (code "118") (name "Net-(U3-REXT)") (class "Default")
      (node (ref "R60") (pin "2") (pinfunction "2_2") (pintype "passive"))
      (node (ref "U3") (pin "9") (pinfunction "REXT_9") (pintype "passive"))
    )
    (net (code "119") (name "Net-(U3-RXD0)") (class "Default")
      (node (ref "R35") (pin "1") (pinfunction "1_1") (pintype "passive"))
      (node (ref "U3") (pin "13") (pinfunction "RXD0_13") (pintype "output"))
    )
    (net (code "120") (name "Net-(U3-RXD1)") (class "Default")
      (node (ref "R34") (pin "1") (pinfunction "1_1") (pintype "passive"))
      (node (ref "U3") (pin "12") (pinfunction "RXD1_12") (pintype "output"))
    )
    (net (code "121") (name "Net-(U3-RXM)") (class "Default")
      (node (ref "U3") (pin "3") (pinfunction "RXM_3") (pintype "passive"))
      (node (ref "X8") (pin "5") (pinfunction "TRD2-_5_5") (pintype "bidirectional"))
    )
    (net (code "122") (name "Net-(U3-RXP)") (class "Default")
      (node (ref "U3") (pin "4") (pinfunction "RXP_4") (pintype "passive"))
      (node (ref "X8") (pin "4") (pinfunction "TRD2+_4_4") (pintype "bidirectional"))
    )
    (net (code "123") (name "Net-(U3-TXM)") (class "Default")
      (node (ref "U3") (pin "5") (pinfunction "TXM_5") (pintype "passive"))
      (node (ref "X8") (pin "10") (pinfunction "TRD1-_10_10") (pintype "bidirectional"))
    )
    (net (code "124") (name "Net-(U3-TXP)") (class "Default")
      (node (ref "U3") (pin "6") (pinfunction "TXP_6") (pintype "passive"))
      (node (ref "X8") (pin "11") (pinfunction "TRD1+_11_11") (pintype "bidirectional"))
    )
    (net (code "125") (name "Net-(U3-VDD_1.2)") (class "Default")
      (node (ref "C76") (pin "1") (pinfunction "1_1") (pintype "passive"))
      (node (ref "C77") (pin "1") (pinfunction "1_1") (pintype "passive"))
      (node (ref "U3") (pin "1") (pinfunction "VDD_1.2_1") (pintype "power_in"))
    )
    (net (code "126") (name "Net-(VR2-EN)") (class "Default")
      (node (ref "R13") (pin "2") (pinfunction "2_2") (pintype "passive"))
      (node (ref "R14") (pin "2") (pinfunction "2_2") (pintype "passive"))
      (node (ref "VR2") (pin "3") (pinfunction "EN_3") (pintype "bidirectional"))
    )
    (net (code "127") (name "Net-(VR2-FB)") (class "Default")
      (node (ref "C32") (pin "1") (pinfunction "1_1") (pintype "passive"))
      (node (ref "R11") (pin "1") (pinfunction "1_1") (pintype "passive"))
      (node (ref "R15") (pin "2") (pinfunction "2_2") (pintype "passive"))
      (node (ref "VR2") (pin "6") (pinfunction "FB_6") (pintype "bidirectional"))
    )
    (net (code "128") (name "Net-(VR2-RON)") (class "Default")
      (node (ref "R12") (pin "2") (pinfunction "2_2") (pintype "passive"))
      (node (ref "VR2") (pin "2") (pinfunction "RON_2") (pintype "bidirectional"))
    )
    (net (code "129") (name "Net-(VR2-SS)") (class "Default")
      (node (ref "C33") (pin "2") (pinfunction "2_2") (pintype "passive"))
      (node (ref "VR2") (pin "5") (pinfunction "SS_5") (pintype "bidirectional"))
    )
    (net (code "130") (name "Net-(X8-LED2_20)") (class "Default")
      (node (ref "R59") (pin "2") (pinfunction "2_2") (pintype "passive"))
      (node (ref "X8") (pin "20") (pinfunction "LED2_20_20") (pintype "input"))
    )
    (net (code "131") (name "Net-(X8-TRCT1_12)") (class "Default")
      (node (ref "C99") (pin "2") (pinfunction "2_2") (pintype "passive"))
      (node (ref "X8") (pin "12") (pinfunction "TRCT1_12_12") (pintype "input"))
    )
    (net (code "132") (name "Net-(X8-TRCT2_6)") (class "Default")
      (node (ref "C54") (pin "2") (pinfunction "2_2") (pintype "passive"))
      (node (ref "X8") (pin "6") (pinfunction "TRCT2_6_6") (pintype "input"))
    )
    (net (code "133") (name "OSC_IN") (class "Default")
      (node (ref "C43") (pin "1") (pinfunction "1_1") (pintype "passive"))
      (node (ref "Q1") (pin "1") (pinfunction "1_1") (pintype "passive"))
      (node (ref "U1") (pin "12") (pinfunction "PH0_12") (pintype "bidirectional"))
    )
    (net (code "134") (name "OSC_OUT") (class "Default")
      (node (ref "C45") (pin "1") (pinfunction "1_1") (pintype "passive"))
      (node (ref "Q1") (pin "3") (pinfunction "2_3") (pintype "passive"))
      (node (ref "U1") (pin "13") (pinfunction "PH1_13") (pintype "bidirectional"))
    )
    (net (code "135") (name "POE+") (class "Default")
      (node (ref "C129") (pin "1") (pinfunction "1_1") (pintype "passive"))
      (node (ref "C130") (pin "1") (pinfunction "1_1") (pintype "passive"))
      (node (ref "C133") (pin "1") (pinfunction "1_1") (pintype "passive"))
      (node (ref "C48") (pin "1") (pinfunction "1_1") (pintype "passive"))
      (node (ref "C51") (pin "1") (pinfunction "1_1") (pintype "passive"))
      (node (ref "C53") (pin "+") (pinfunction "+_+") (pintype "passive"))
      (node (ref "D3") (pin "P$2") (pinfunction "C_P$2") (pintype "passive"))
      (node (ref "D4") (pin "C") (pinfunction "C_C") (pintype "passive"))
      (node (ref "IC2") (pin "21") (pinfunction "AGND_21") (pintype "bidirectional"))
      (node (ref "L2") (pin "2") (pinfunction "2_2") (pintype "passive"))
      (node (ref "POE") (pin "9") (pinfunction "+VOUT_9") (pintype "power_in"))
      (node (ref "R99") (pin "1") (pinfunction "1_1") (pintype "passive"))
      (node (ref "X8") (pin "13") (pinfunction "VC12_13_13") (pintype "input"))
    )
    (net (code "136") (name "POE-") (class "Default")
      (node (ref "C129") (pin "2") (pinfunction "2_2") (pintype "passive"))
      (node (ref "C130") (pin "2") (pinfunction "2_2") (pintype "passive"))
      (node (ref "C133") (pin "2") (pinfunction "2_2") (pintype "passive"))
      (node (ref "C44") (pin "2") (pinfunction "2_2") (pintype "passive"))
      (node (ref "C48") (pin "2") (pinfunction "2_2") (pintype "passive"))
      (node (ref "C53") (pin "-") (pinfunction "-_-") (pintype "passive"))
      (node (ref "IC2") (pin "1") (pinfunction "VEE_1") (pintype "bidirectional"))
      (node (ref "IC2") (pin "10") (pinfunction "VEE_10") (pintype "bidirectional"))
      (node (ref "IC2") (pin "11") (pinfunction "VEE_11") (pintype "bidirectional"))
      (node (ref "IC2") (pin "12") (pinfunction "VEE_DIG_12") (pintype "bidirectional"))
      (node (ref "IC2") (pin "13") (pinfunction "LEGACY_13") (pintype "bidirectional"))
      (node (ref "IC2") (pin "15") (pinfunction "VEE_15") (pintype "bidirectional"))
      (node (ref "IC2") (pin "19") (pinfunction "OSC_19") (pintype "bidirectional"))
      (node (ref "IC2") (pin "2") (pinfunction "VEE_2") (pintype "bidirectional"))
      (node (ref "IC2") (pin "3") (pinfunction "VEE_3") (pintype "bidirectional"))
      (node (ref "IC2") (pin "6") (pinfunction "2-EVENT_6") (pintype "bidirectional"))
      (node (ref "IC2") (pin "7") (pinfunction "MIDSPAN_7") (pintype "bidirectional"))
      (node (ref "IC2") (pin "8") (pinfunction "VEE_8") (pintype "bidirectional"))
      (node (ref "IC2") (pin "9") (pinfunction "VEE_9") (pintype "bidirectional"))
      (node (ref "IC2") (pin "PAD") (pinfunction "VEE_PAD") (pintype "bidirectional"))
      (node (ref "POE") (pin "5") (pinfunction "-VOUT_5") (pintype "power_in"))
      (node (ref "R23") (pin "2") (pinfunction "2_2") (pintype "passive"))
      (node (ref "R24") (pin "2") (pinfunction "2_2") (pintype "passive"))
    )
    (net (code "137") (name "POE_LED+") (class "Default")
      (node (ref "L2") (pin "1") (pinfunction "1_1") (pintype "passive"))
      (node (ref "X8") (pin "17") (pinfunction "LED1_17_17") (pintype "input"))
    )
    (net (code "138") (name "POE_LED-") (class "Default")
      (node (ref "D3") (pin "P$1") (pinfunction "A_P$1") (pintype "passive"))
      (node (ref "R_LED") (pin "2") (pinfunction "2_2") (pintype "passive"))
      (node (ref "X8") (pin "18") (pinfunction "LED1_18_18") (pintype "input"))
    )
    (net (code "139") (name "PSE_OUTPUT") (class "Default")
      (node (ref "C51") (pin "2") (pinfunction "2_2") (pintype "passive"))
      (node (ref "D4") (pin "A") (pinfunction "A_A") (pintype "passive"))
      (node (ref "D5") (pin "P$1") (pinfunction "A_P$1") (pintype "passive"))
      (node (ref "IC2") (pin "25") (pinfunction "OUTP_25") (pintype "bidirectional"))
      (node (ref "IC2") (pin "26") (pinfunction "OUT_26") (pintype "bidirectional"))
      (node (ref "IC2") (pin "27") (pinfunction "OUT_27") (pintype "bidirectional"))
      (node (ref "R99") (pin "2") (pinfunction "2_2") (pintype "passive"))
      (node (ref "X8") (pin "14") (pinfunction "VC36_14_14") (pintype "input"))
    )
    (net (code "140") (name "PWM_AXIS3_U_OUT") (class "Default")
      (node (ref "R37") (pin "2") (pinfunction "2_2") (pintype "passive"))
      (node (ref "U1") (pin "64") (pinfunction "PC7_64") (pintype "bidirectional"))
    )
    (net (code "141") (name "PWM_AXIS3_V_OUT") (class "Default")
      (node (ref "R50") (pin "2") (pinfunction "2_2") (pintype "passive"))
      (node (ref "U1") (pin "63") (pinfunction "PC6_63") (pintype "bidirectional"))
    )
    (net (code "142") (name "PWM_AXIS4_U_OUT") (class "Default")
      (node (ref "R40") (pin "2") (pinfunction "2_2") (pintype "passive"))
      (node (ref "U1") (pin "66") (pinfunction "PC9_66") (pintype "bidirectional"))
    )
    (net (code "143") (name "PWM_AXIS4_V_OUT") (class "Default")
      (node (ref "R39") (pin "2") (pinfunction "2_2") (pintype "passive"))
      (node (ref "U1") (pin "65") (pinfunction "PC8_65") (pintype "bidirectional"))
    )
    (net (code "144") (name "PWM_LAT_U_OUT") (class "Default")
      (node (ref "R48") (pin "2") (pinfunction "2_2") (pintype "passive"))
      (node (ref "U1") (pin "62") (pinfunction "PD15_62") (pintype "bidirectional"))
    )
    (net (code "145") (name "PWM_LAT_V_OUT") (class "Default")
      (node (ref "R47") (pin "2") (pinfunction "2_2") (pintype "passive"))
      (node (ref "U1") (pin "61") (pinfunction "PD14_61") (pintype "bidirectional"))
    )
    (net (code "146") (name "PWM_VERT_U_OUT") (class "Default")
      (node (ref "R46") (pin "2") (pinfunction "2_2") (pintype "passive"))
      (node (ref "U1") (pin "60") (pinfunction "PD13_60") (pintype "bidirectional"))
    )
    (net (code "147") (name "PWM_VERT_V_OUT") (class "Default")
      (node (ref "R45") (pin "2") (pinfunction "2_2") (pintype "passive"))
      (node (ref "U1") (pin "59") (pinfunction "PD12_59") (pintype "bidirectional"))
    )
    (net (code "148") (name "REF_MONITOR") (class "Default")
      (node (ref "C22") (pin "1") (pinfunction "1_1") (pintype "passive"))
      (node (ref "R10") (pin "2") (pinfunction "2_2") (pintype "passive"))
      (node (ref "R16") (pin "2") (pinfunction "2_2") (pintype "passive"))
      (node (ref "U1") (pin "15") (pinfunction "PC0_15") (pintype "bidirectional"))
    )
    (net (code "149") (name "SPI_MISO") (class "Default")
      (node (ref "R20") (pin "2") (pinfunction "2_2") (pintype "passive"))
      (node (ref "U1") (pin "31") (pinfunction "PA6/SPI_MISO_31") (pintype "bidirectional"))
      (node (ref "U1") (pin "38") (pinfunction "PE7_38") (pintype "bidirectional"))
    )
    (net (code "150") (name "SPI_SCK") (class "Default")
      (node (ref "ADC1") (pin "8") (pinfunction "SCK_8") (pintype "input"))
      (node (ref "ADC2") (pin "8") (pinfunction "SCK_8") (pintype "input"))
      (node (ref "ADC3") (pin "8") (pinfunction "SCK_8") (pintype "input"))
      (node (ref "ADC4") (pin "8") (pinfunction "SCK_8") (pintype "input"))
      (node (ref "R32") (pin "1") (pinfunction "1_1") (pintype "passive"))
    )
    (net (code "151") (name "USB_D+") (class "Default")
      (node (ref "R22") (pin "2") (pinfunction "2_2") (pintype "passive"))
      (node (ref "U1") (pin "71") (pinfunction "PA12/OTG_FS_DP_71") (pintype "bidirectional"))
    )
    (net (code "152") (name "USB_D-") (class "Default")
      (node (ref "R21") (pin "2") (pinfunction "2_2") (pintype "passive"))
      (node (ref "U1") (pin "70") (pinfunction "PA11/OTG_FS_DM_70") (pintype "bidirectional"))
    )
    (net (code "153") (name "USB_ID") (class "Default")
      (node (ref "U1") (pin "69") (pinfunction "PA10/OTG_FS_ID_69") (pintype "bidirectional"))
      (node (ref "X4") (pin "4") (pinfunction "4_4") (pintype "passive"))
    )
    (net (code "154") (name "USB_VBUS") (class "Default")
      (node (ref "C46") (pin "1") (pinfunction "1_1") (pintype "passive"))
      (node (ref "U1") (pin "68") (pinfunction "PA9/OTG_FS_VBUS_68") (pintype "bidirectional"))
      (node (ref "X4") (pin "1") (pinfunction "1_1") (pintype "passive"))
    )
    (net (code "155") (name "VDDA_3.3") (class "Default")
      (node (ref "C97") (pin "2") (pinfunction "2_2") (pintype "passive"))
      (node (ref "C98") (pin "2") (pinfunction "2_2") (pintype "passive"))
      (node (ref "L3") (pin "1") (pinfunction "1_1") (pintype "passive"))
      (node (ref "U3") (pin "2") (pinfunction "VDDA_3.3_2") (pintype "power_in"))
    )
    (net (code "156") (name "WATCHDOG_AXIS3_OUT") (class "Default")
      (node (ref "R42") (pin "2") (pinfunction "2_2") (pintype "passive"))
      (node (ref "U1") (pin "82") (pinfunction "PD1_82") (pintype "bidirectional"))
    )
    (net (code "157") (name "WATCHDOG_AXIS4_OUT") (class "Default")
      (node (ref "R44") (pin "2") (pinfunction "2_2") (pintype "passive"))
      (node (ref "U1") (pin "84") (pinfunction "PD3_84") (pintype "bidirectional"))
    )
    (net (code "158") (name "WATCHDOG_LAT_OUT") (class "Default")
      (node (ref "R49") (pin "2") (pinfunction "2_2") (pintype "passive"))
      (node (ref "U1") (pin "57") (pinfunction "PD10_57") (pintype "bidirectional"))
    )
    (net (code "159") (name "WATCHDOG_VERT_OUT") (class "Default")
      (node (ref "R52") (pin "2") (pinfunction "2_2") (pintype "passive"))
      (node (ref "U1") (pin "86") (pinfunction "PD5_86") (pintype "bidirectional"))
    )
    (net (code "160") (name "unconnected-(J22-PadNC{slash}KEY)") (class "Default")
      (node (ref "J22") (pin "NC/KEY") (pinfunction "NC/KEY_NC/KEY") (pintype "passive"))
    )
    (net (code "161") (name "unconnected-(POE-ON{slash}OFF-Pad2)") (class "Default")
      (node (ref "POE") (pin "2") (pinfunction "ON/OFF_2") (pintype "input"))
    )
    (net (code "162") (name "unconnected-(REF1-COMP-Pad7)") (class "Default")
      (node (ref "REF1") (pin "7") (pinfunction "COMP_7") (pintype "bidirectional"))
    )
    (net (code "163") (name "unconnected-(REF1-NIC-Pad3)") (class "Default")
      (node (ref "REF1") (pin "3") (pinfunction "NIC_3") (pintype "bidirectional"))
    )
    (net (code "164") (name "unconnected-(REF1-TP-Pad1)") (class "Default")
      (node (ref "REF1") (pin "1") (pinfunction "TP_1") (pintype "bidirectional"))
    )
    (net (code "165") (name "unconnected-(REF1-TP-Pad8)") (class "Default")
      (node (ref "REF1") (pin "8") (pinfunction "TP_8") (pintype "bidirectional"))
    )
    (net (code "166") (name "unconnected-(REF1-TRIM-Pad5)") (class "Default")
      (node (ref "REF1") (pin "5") (pinfunction "TRIM_5") (pintype "bidirectional"))
    )
    (net (code "167") (name "unconnected-(U1A-PB0{slash}ETH_MII_RXD2-Pad35)") (class "Default")
      (node (ref "U1") (pin "35") (pinfunction "PB0/ETH_MII_RXD2_35") (pintype "bidirectional"))
    )
    (net (code "168") (name "unconnected-(U1A-PB1{slash}ETH_MII_RXD3-Pad36)") (class "Default")
      (node (ref "U1") (pin "36") (pinfunction "PB1/ETH_MII_RXD3_36") (pintype "bidirectional"))
    )
    (net (code "169") (name "unconnected-(U1A-PB2-Pad37)") (class "Default")
      (node (ref "U1") (pin "37") (pinfunction "PB2_37") (pintype "bidirectional"))
    )
    (net (code "170") (name "unconnected-(U1A-PB4{slash}NJTRST-Pad90)") (class "Default")
      (node (ref "U1") (pin "90") (pinfunction "PB4/NJTRST_90") (pintype "bidirectional"))
    )
    (net (code "171") (name "unconnected-(U1A-PB5{slash}SPI1_MOSI-Pad91)") (class "Default")
      (node (ref "U1") (pin "91") (pinfunction "PB5/SPI1_MOSI_91") (pintype "bidirectional"))
    )
    (net (code "172") (name "unconnected-(U1A-PB6-Pad92)") (class "Default")
      (node (ref "U1") (pin "92") (pinfunction "PB6_92") (pintype "bidirectional"))
    )
    (net (code "173") (name "unconnected-(U1A-PB7-Pad93)") (class "Default")
      (node (ref "U1") (pin "93") (pinfunction "PB7_93") (pintype "bidirectional"))
    )
    (net (code "174") (name "unconnected-(U1A-PB8{slash}ETH_MII_TXD3-Pad95)") (class "Default")
      (node (ref "U1") (pin "95") (pinfunction "PB8/ETH_MII_TXD3_95") (pintype "bidirectional"))
    )
    (net (code "175") (name "unconnected-(U1A-PB9-Pad96)") (class "Default")
      (node (ref "U1") (pin "96") (pinfunction "PB9_96") (pintype "bidirectional"))
    )
    (net (code "176") (name "unconnected-(U1A-PB10{slash}ETH_MII_RX_ER-Pad47)") (class "Default")
      (node (ref "U1") (pin "47") (pinfunction "PB10/ETH_MII_RX_ER_47") (pintype "bidirectional"))
    )
    (net (code "177") (name "unconnected-(U1A-PB15-Pad54)") (class "Default")
      (node (ref "U1") (pin "54") (pinfunction "PB15_54") (pintype "bidirectional"))
    )
    (net (code "178") (name "unconnected-(U1A-PC2{slash}ETH_MII_TXD2-Pad17)") (class "Default")
      (node (ref "U1") (pin "17") (pinfunction "PC2/ETH_MII_TXD2_17") (pintype "bidirectional"))
    )
    (net (code "179") (name "unconnected-(U1A-PC3{slash}ETH_MII_TX_CLK-Pad18)") (class "Default")
      (node (ref "U1") (pin "18") (pinfunction "PC3/ETH_MII_TX_CLK_18") (pintype "bidirectional"))
    )
    (net (code "180") (name "unconnected-(U1A-PC10-Pad78)") (class "Default")
      (node (ref "U1") (pin "78") (pinfunction "PC10_78") (pintype "bidirectional"))
    )
    (net (code "181") (name "unconnected-(U1A-PC11-Pad79)") (class "Default")
      (node (ref "U1") (pin "79") (pinfunction "PC11_79") (pintype "bidirectional"))
    )
    (net (code "182") (name "unconnected-(U1A-PC13-Pad7)") (class "Default")
      (node (ref "U1") (pin "7") (pinfunction "PC13_7") (pintype "bidirectional"))
    )
    (net (code "183") (name "unconnected-(U1A-PC15-Pad9)") (class "Default")
      (node (ref "U1") (pin "9") (pinfunction "PC15_9") (pintype "bidirectional"))
    )
    (net (code "184") (name "unconnected-(U1A-PD4-Pad85)") (class "Default")
      (node (ref "U1") (pin "85") (pinfunction "PD4_85") (pintype "bidirectional"))
    )
    (net (code "185") (name "unconnected-(U1A-PD7-Pad88)") (class "Default")
      (node (ref "U1") (pin "88") (pinfunction "PD7_88") (pintype "bidirectional"))
    )
    (net (code "186") (name "unconnected-(U1A-PD8-Pad55)") (class "Default")
      (node (ref "U1") (pin "55") (pinfunction "PD8_55") (pintype "bidirectional"))
    )
    (net (code "187") (name "unconnected-(U1A-PD9-Pad56)") (class "Default")
      (node (ref "U1") (pin "56") (pinfunction "PD9_56") (pintype "bidirectional"))
    )
    (net (code "188") (name "unconnected-(U1A-PE8-Pad39)") (class "Default")
      (node (ref "U1") (pin "39") (pinfunction "PE8_39") (pintype "bidirectional"))
    )
    (net (code "189") (name "unconnected-(U1A-PE12-Pad43)") (class "Default")
      (node (ref "U1") (pin "43") (pinfunction "PE12_43") (pintype "bidirectional"))
    )
    (net (code "190") (name "unconnected-(U1A-PE14-Pad45)") (class "Default")
      (node (ref "U1") (pin "45") (pinfunction "PE14_45") (pintype "bidirectional"))
    )
    (net (code "191") (name "unconnected-(U1A-PE15-Pad46)") (class "Default")
      (node (ref "U1") (pin "46") (pinfunction "PE15_46") (pintype "bidirectional"))
    )
    (net (code "192") (name "unconnected-(U3-RXER-Pad17)") (class "Default")
      (node (ref "U3") (pin "17") (pinfunction "RXER_17") (pintype "output"))
    )
    (net (code "193") (name "unconnected-(U3-XO-Pad7)") (class "Default")
      (node (ref "U3") (pin "7") (pinfunction "XO_7") (pintype "output"))
    )
    (net (code "194") (name "unconnected-(VR3-NC-Pad5)") (class "Default")
      (node (ref "VR3") (pin "5") (pinfunction "NC_5") (pintype "bidirectional"))
    )
    (net (code "195") (name "unconnected-(VR8-DELAY-Pad4)") (class "Default")
      (node (ref "VR8") (pin "4") (pinfunction "DELAY_4") (pintype "output"))
    )
    (net (code "196") (name "unconnected-(VR8-RESET-Pad2)") (class "Default")
      (node (ref "VR8") (pin "2") (pinfunction "RESET_2") (pintype "output"))
    )
    (net (code "197") (name "unconnected-(X8-VC45_15-Pad15)") (class "Default")
      (node (ref "X8") (pin "15") (pinfunction "VC45_15_15") (pintype "input"))
    )
    (net (code "198") (name "unconnected-(X8-VC78_16-Pad16)") (class "Default")
      (node (ref "X8") (pin "16") (pinfunction "VC78_16_16") (pintype "input"))
    )
  )
)
